# NO_1.net
KiCad netlist of a schematic drawn in Altium Designer
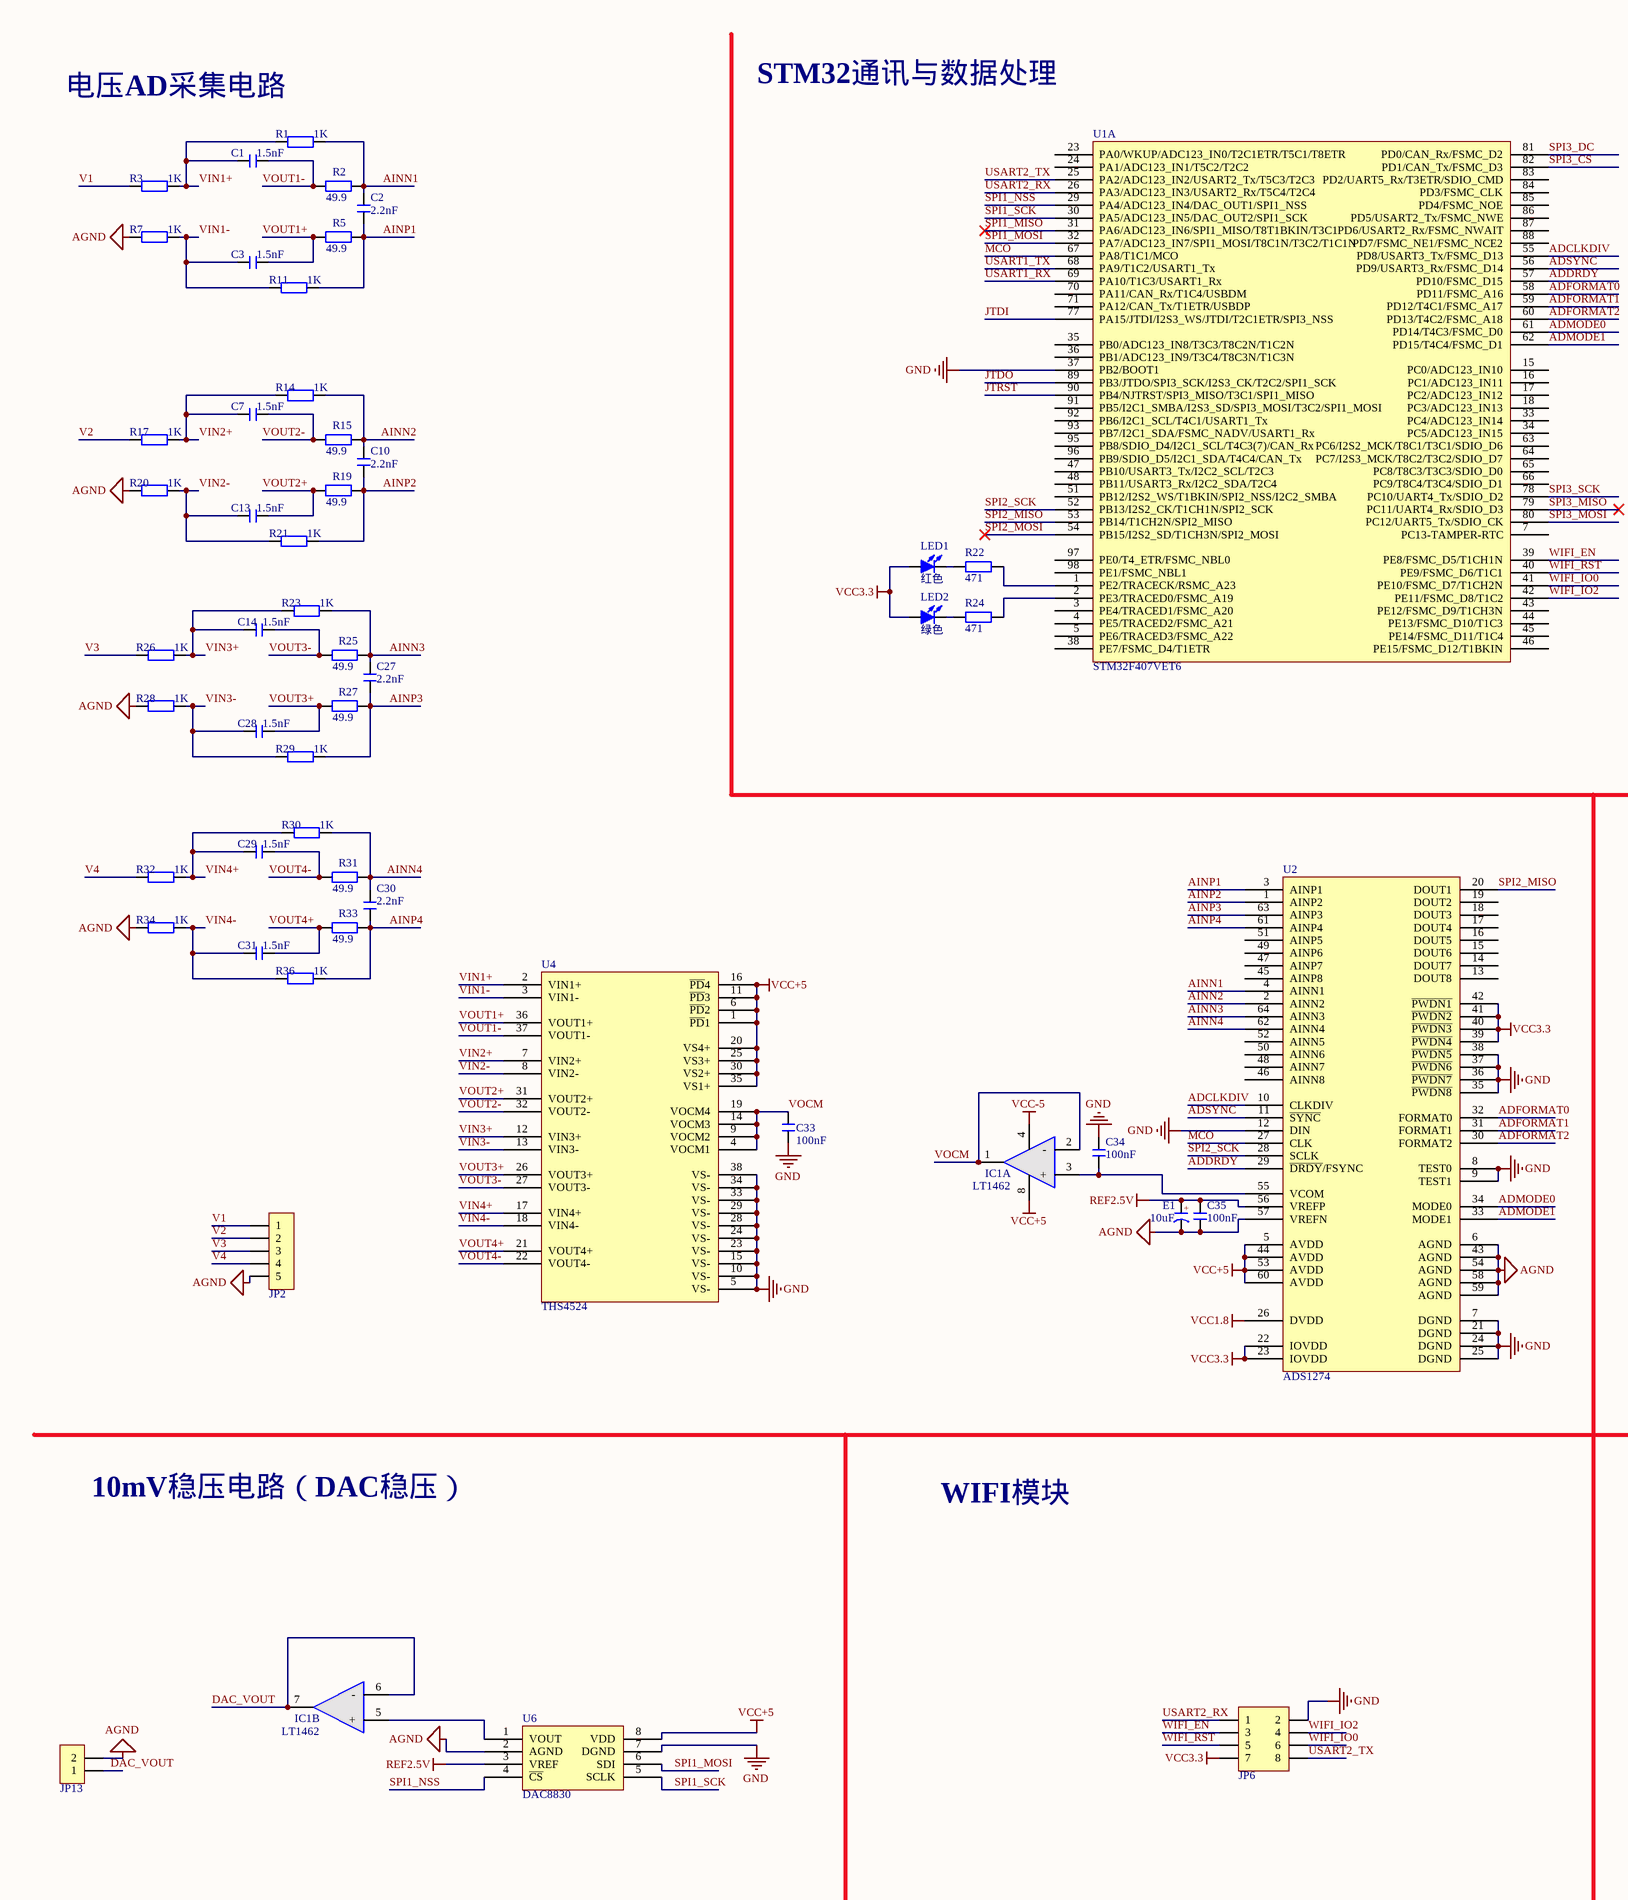
[diagram p0: NO.1 采集板.SchDoc, left]
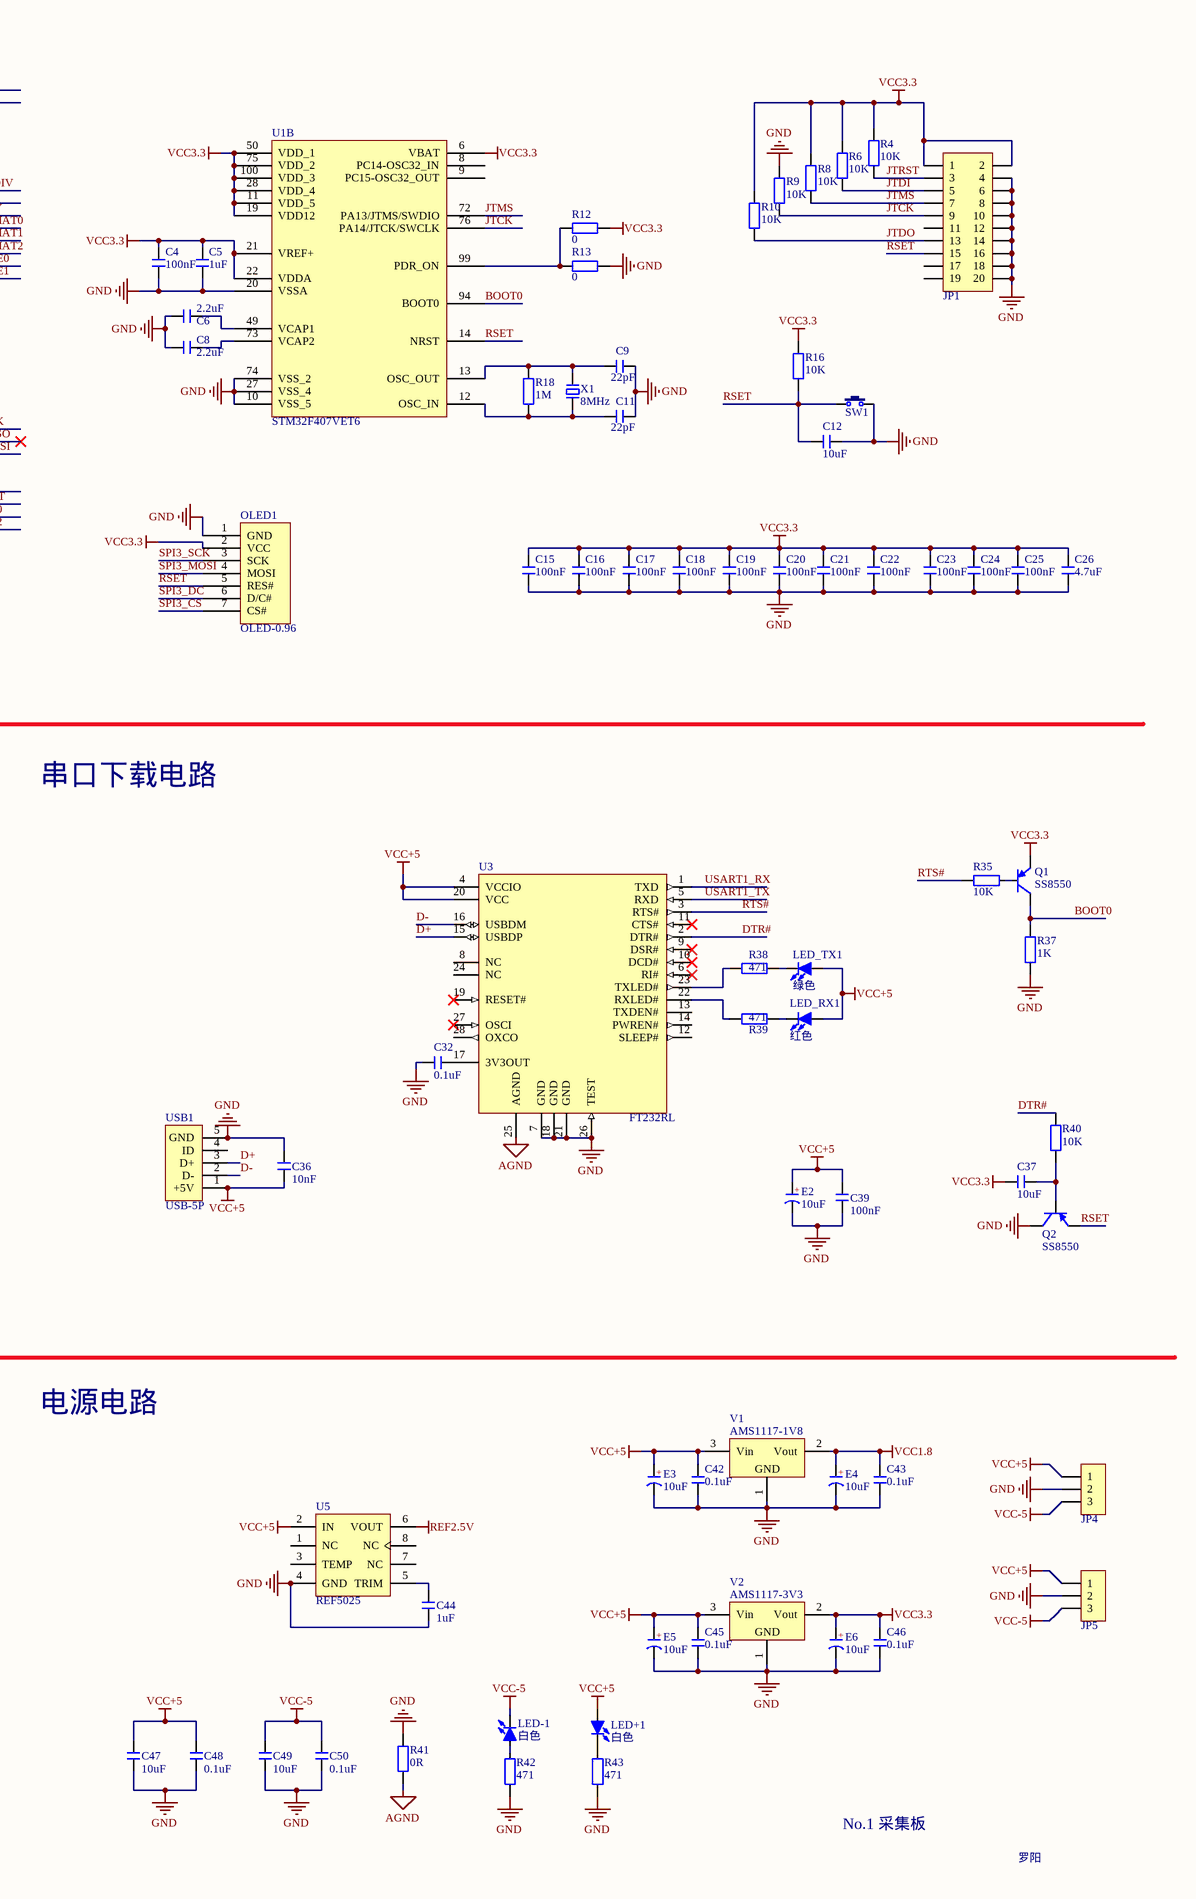
[diagram p1: NO.1 采集板.SchDoc, right]

(export (version "E")
  (design (tool "Eeschema 10.0.6"))
  (components
    (comp (ref "C1")
      (value "1.5nF")
      (footprint "C 0805_M")
      (description "无极性贴片电容")
      (fields (field (name "版权归属") "源创客"))
      (libsource (lib "3.1   - 电阻-电容-电感") (part "C"))
    )
    (comp (ref "C2")
      (value "2.2nF")
      (footprint "C 0805_M")
      (description "无极性贴片电容")
      (fields (field (name "版权归属") "源创客"))
      (libsource (lib "3.1   - 电阻-电容-电感") (part "C"))
    )
    (comp (ref "C3")
      (value "1.5nF")
      (footprint "C 0805_M")
      (description "无极性贴片电容")
      (fields (field (name "版权归属") "源创客"))
      (libsource (lib "3.1   - 电阻-电容-电感") (part "C"))
    )
    (comp (ref "C4")
      (value "100nF")
      (footprint "C 0805_M")
      (description "无极性贴片电容")
      (fields (field (name "版权归属") "源创客"))
      (libsource (lib "3.1   - 电阻-电容-电感") (part "C"))
    )
    (comp (ref "C5")
      (value "1uF")
      (footprint "C 0805_M")
      (description "无极性贴片电容")
      (fields (field (name "版权归属") "源创客"))
      (libsource (lib "3.1   - 电阻-电容-电感") (part "C"))
    )
    (comp (ref "C6")
      (value "2.2uF")
      (footprint "C 0805_M")
      (description "无极性贴片电容")
      (fields (field (name "版权归属") "源创客"))
      (libsource (lib "3.1   - 电阻-电容-电感") (part "C"))
    )
    (comp (ref "C7")
      (value "1.5nF")
      (footprint "C 0805_M")
      (description "无极性贴片电容")
      (fields (field (name "版权归属") "源创客"))
      (libsource (lib "3.1   - 电阻-电容-电感") (part "C"))
    )
    (comp (ref "C8")
      (value "2.2uF")
      (footprint "C 0805_M")
      (description "无极性贴片电容")
      (fields (field (name "版权归属") "源创客"))
      (libsource (lib "3.1   - 电阻-电容-电感") (part "C"))
    )
    (comp (ref "C9")
      (value "22pF")
      (footprint "C 0805_M")
      (description "无极性贴片电容")
      (fields (field (name "版权归属") "源创客"))
      (libsource (lib "3.1   - 电阻-电容-电感") (part "C"))
    )
    (comp (ref "C10")
      (value "2.2nF")
      (footprint "C 0805_M")
      (description "无极性贴片电容")
      (fields (field (name "版权归属") "源创客"))
      (libsource (lib "3.1   - 电阻-电容-电感") (part "C"))
    )
    (comp (ref "C11")
      (value "22pF")
      (footprint "C 0805_M")
      (description "无极性贴片电容")
      (fields (field (name "版权归属") "源创客"))
      (libsource (lib "3.1   - 电阻-电容-电感") (part "C"))
    )
    (comp (ref "C12")
      (value "10uF")
      (footprint "C 0805_M")
      (description "无极性贴片电容")
      (fields (field (name "版权归属") "源创客"))
      (libsource (lib "3.1   - 电阻-电容-电感") (part "C"))
    )
    (comp (ref "C13")
      (value "1.5nF")
      (footprint "C 0805_M")
      (description "无极性贴片电容")
      (fields (field (name "版权归属") "源创客"))
      (libsource (lib "3.1   - 电阻-电容-电感") (part "C"))
    )
    (comp (ref "C14")
      (value "1.5nF")
      (footprint "C 0805_M")
      (description "无极性贴片电容")
      (fields (field (name "版权归属") "源创客"))
      (libsource (lib "3.1   - 电阻-电容-电感") (part "C"))
    )
    (comp (ref "C15")
      (value "100nF")
      (footprint "C 0805_M")
      (description "无极性贴片电容")
      (fields (field (name "版权归属") "源创客"))
      (libsource (lib "3.1   - 电阻-电容-电感") (part "C"))
    )
    (comp (ref "C16")
      (value "100nF")
      (footprint "C 0805_M")
      (description "无极性贴片电容")
      (fields (field (name "版权归属") "源创客"))
      (libsource (lib "3.1   - 电阻-电容-电感") (part "C"))
    )
    (comp (ref "C17")
      (value "100nF")
      (footprint "C 0805_M")
      (description "无极性贴片电容")
      (fields (field (name "版权归属") "源创客"))
      (libsource (lib "3.1   - 电阻-电容-电感") (part "C"))
    )
    (comp (ref "C18")
      (value "100nF")
      (footprint "C 0805_M")
      (description "无极性贴片电容")
      (fields (field (name "版权归属") "源创客"))
      (libsource (lib "3.1   - 电阻-电容-电感") (part "C"))
    )
    (comp (ref "C19")
      (value "100nF")
      (footprint "C 0805_M")
      (description "无极性贴片电容")
      (fields (field (name "版权归属") "源创客"))
      (libsource (lib "3.1   - 电阻-电容-电感") (part "C"))
    )
    (comp (ref "C20")
      (value "100nF")
      (footprint "C 0805_M")
      (description "无极性贴片电容")
      (fields (field (name "版权归属") "源创客"))
      (libsource (lib "3.1   - 电阻-电容-电感") (part "C"))
    )
    (comp (ref "C21")
      (value "100nF")
      (footprint "C 0805_M")
      (description "无极性贴片电容")
      (fields (field (name "版权归属") "源创客"))
      (libsource (lib "3.1   - 电阻-电容-电感") (part "C"))
    )
    (comp (ref "C22")
      (value "100nF")
      (footprint "C 0805_M")
      (description "无极性贴片电容")
      (fields (field (name "版权归属") "源创客"))
      (libsource (lib "3.1   - 电阻-电容-电感") (part "C"))
    )
    (comp (ref "C23")
      (value "100nF")
      (footprint "C 0805_M")
      (description "无极性贴片电容")
      (fields (field (name "版权归属") "源创客"))
      (libsource (lib "3.1   - 电阻-电容-电感") (part "C"))
    )
    (comp (ref "C24")
      (value "100nF")
      (footprint "C 0805_M")
      (description "无极性贴片电容")
      (fields (field (name "版权归属") "源创客"))
      (libsource (lib "3.1   - 电阻-电容-电感") (part "C"))
    )
    (comp (ref "C25")
      (value "100nF")
      (footprint "C 0805_M")
      (description "无极性贴片电容")
      (fields (field (name "版权归属") "源创客"))
      (libsource (lib "3.1   - 电阻-电容-电感") (part "C"))
    )
    (comp (ref "C26")
      (value "4.7uF")
      (footprint "C 0805_M")
      (description "无极性贴片电容")
      (fields (field (name "版权归属") "源创客"))
      (libsource (lib "3.1   - 电阻-电容-电感") (part "C"))
    )
    (comp (ref "C27")
      (value "2.2nF")
      (footprint "C 0805_M")
      (description "无极性贴片电容")
      (fields (field (name "版权归属") "源创客"))
      (libsource (lib "3.1   - 电阻-电容-电感") (part "C"))
    )
    (comp (ref "C28")
      (value "1.5nF")
      (footprint "C 0805_M")
      (description "无极性贴片电容")
      (fields (field (name "版权归属") "源创客"))
      (libsource (lib "3.1   - 电阻-电容-电感") (part "C"))
    )
    (comp (ref "C29")
      (value "1.5nF")
      (footprint "C 0805_M")
      (description "无极性贴片电容")
      (fields (field (name "版权归属") "源创客"))
      (libsource (lib "3.1   - 电阻-电容-电感") (part "C"))
    )
    (comp (ref "C30")
      (value "2.2nF")
      (footprint "C 0805_M")
      (description "无极性贴片电容")
      (fields (field (name "版权归属") "源创客"))
      (libsource (lib "3.1   - 电阻-电容-电感") (part "C"))
    )
    (comp (ref "C31")
      (value "1.5nF")
      (footprint "C 0805_M")
      (description "无极性贴片电容")
      (fields (field (name "版权归属") "源创客"))
      (libsource (lib "3.1   - 电阻-电容-电感") (part "C"))
    )
    (comp (ref "C32")
      (value "0.1uF")
      (footprint "C 0805_M")
      (description "无极性贴片电容")
      (fields (field (name "版权归属") "源创客"))
      (libsource (lib "3.1   - 电阻-电容-电感") (part "C"))
    )
    (comp (ref "C33")
      (value "100nF")
      (footprint "C 0805_M")
      (description "无极性贴片电容")
      (fields (field (name "版权归属") "源创客"))
      (libsource (lib "3.1   - 电阻-电容-电感") (part "C"))
    )
    (comp (ref "C34")
      (value "100nF")
      (footprint "C 0805_M")
      (description "无极性贴片电容")
      (fields (field (name "版权归属") "源创客"))
      (libsource (lib "3.1   - 电阻-电容-电感") (part "C"))
    )
    (comp (ref "C35")
      (value "100nF")
      (footprint "C 0805_M")
      (description "无极性贴片电容")
      (fields (field (name "版权归属") "源创客"))
      (libsource (lib "3.1   - 电阻-电容-电感") (part "C"))
    )
    (comp (ref "C36")
      (value "10nF")
      (footprint "C 0805_M")
      (description "无极性贴片电容")
      (fields (field (name "版权归属") "源创客"))
      (libsource (lib "3.1   - 电阻-电容-电感") (part "C"))
    )
    (comp (ref "C37")
      (value "10uF")
      (footprint "C 0805_M")
      (description "无极性贴片电容")
      (fields (field (name "版权归属") "源创客"))
      (libsource (lib "3.1   - 电阻-电容-电感") (part "C"))
    )
    (comp (ref "C39")
      (value "100nF")
      (footprint "C 0805_M")
      (description "无极性贴片电容")
      (fields (field (name "版权归属") "源创客"))
      (libsource (lib "3.1   - 电阻-电容-电感") (part "C"))
    )
    (comp (ref "C42")
      (value "0.1uF")
      (footprint "C 0805_M")
      (description "无极性贴片电容")
      (fields (field (name "版权归属") "源创客"))
      (libsource (lib "3.1   - 电阻-电容-电感") (part "C"))
    )
    (comp (ref "C43")
      (value "0.1uF")
      (footprint "C 0805_M")
      (description "无极性贴片电容")
      (fields (field (name "版权归属") "源创客"))
      (libsource (lib "3.1   - 电阻-电容-电感") (part "C"))
    )
    (comp (ref "C44")
      (value "1uF")
      (footprint "C 0805_M")
      (description "无极性贴片电容")
      (fields (field (name "版权归属") "源创客"))
      (libsource (lib "3.1   - 电阻-电容-电感") (part "C"))
    )
    (comp (ref "C45")
      (value "0.1uF")
      (footprint "C 0805_M")
      (description "无极性贴片电容")
      (fields (field (name "版权归属") "源创客"))
      (libsource (lib "3.1   - 电阻-电容-电感") (part "C"))
    )
    (comp (ref "C46")
      (value "0.1uF")
      (footprint "C 0805_M")
      (description "无极性贴片电容")
      (fields (field (name "版权归属") "源创客"))
      (libsource (lib "3.1   - 电阻-电容-电感") (part "C"))
    )
    (comp (ref "C47")
      (value "10uF")
      (footprint "C 0805_M")
      (description "无极性贴片电容")
      (fields (field (name "版权归属") "源创客"))
      (libsource (lib "3.1   - 电阻-电容-电感") (part "C"))
    )
    (comp (ref "C48")
      (value "0.1uF")
      (footprint "C 0805_M")
      (description "无极性贴片电容")
      (fields (field (name "版权归属") "源创客"))
      (libsource (lib "3.1   - 电阻-电容-电感") (part "C"))
    )
    (comp (ref "C49")
      (value "10uF")
      (footprint "C 0805_M")
      (description "无极性贴片电容")
      (fields (field (name "版权归属") "源创客"))
      (libsource (lib "3.1   - 电阻-电容-电感") (part "C"))
    )
    (comp (ref "C50")
      (value "0.1uF")
      (footprint "C 0805_M")
      (description "无极性贴片电容")
      (fields (field (name "版权归属") "源创客"))
      (libsource (lib "3.1   - 电阻-电容-电感") (part "C"))
    )
    (comp (ref "E1")
      (value "10uF")
      (footprint "CD A(3216)")
      (description "贴片钽电容")
      (fields (field (name "版权归属") "源创客"))
      (libsource (lib "3.1   - 电阻-电容-电感") (part "C-CD"))
    )
    (comp (ref "E2")
      (value "10uF")
      (footprint "CD A(3216)")
      (description "贴片电解电容")
      (fields (field (name "版权归属") "源创客"))
      (libsource (lib "3.1   - 电阻-电容-电感") (part "C-CM"))
    )
    (comp (ref "E3")
      (value "10uF")
      (footprint "CD A(3216)")
      (description "贴片钽电容")
      (fields (field (name "版权归属") "源创客"))
      (libsource (lib "3.1   - 电阻-电容-电感") (part "C-CD"))
    )
    (comp (ref "E4")
      (value "10uF")
      (footprint "CD A(3216)")
      (description "贴片钽电容")
      (fields (field (name "版权归属") "源创客"))
      (libsource (lib "3.1   - 电阻-电容-电感") (part "C-CD"))
    )
    (comp (ref "E5")
      (value "10uF")
      (footprint "CD A(3216)")
      (description "贴片钽电容")
      (fields (field (name "版权归属") "源创客"))
      (libsource (lib "3.1   - 电阻-电容-电感") (part "C-CD"))
    )
    (comp (ref "E6")
      (value "10uF")
      (footprint "CD A(3216)")
      (description "贴片钽电容")
      (fields (field (name "版权归属") "源创客"))
      (libsource (lib "3.1   - 电阻-电容-电感") (part "C-CD"))
    )
    (comp (ref "IC1")
      (value "LT1462")
      (footprint "SOP8_N")
      (description "双运放")
      (fields (field (name "版权归属") "源创客"))
      (libsource (lib "1.1   - IC芯片") (part "LT1678"))
    )
    (comp (ref "JP1")
      (value "Header 2X10")
      (footprint "IDC2.54-LI-2x10P")
      (description "10*2P接插件")
      (fields (field (name "版权归属") "源创客"))
      (libsource (lib "4.5   - 接插件-脚距2.54") (part "Header 10X2"))
    )
    (comp (ref "JP2")
      (value "HDR-1X5")
      (footprint "XH2.54-WI-5P")
      (description "5P接插件")
      (fields (field (name "版权归属") "源创客"))
      (libsource (lib "4.5   - 接插件-脚距2.54") (part "Header 5"))
    )
    (comp (ref "JP4")
      (value "HDR-1X3")
      (footprint "XH2.54-WI-3P")
      (description "3P接插件")
      (fields (field (name "版权归属") "源创客"))
      (libsource (lib "4.2   - 接插件-脚距1.25") (part "Header 3"))
    )
    (comp (ref "JP5")
      (value "HDR-1X3")
      (footprint "XH2.54-WI-3P")
      (description "3P接插件")
      (fields (field (name "版权归属") "源创客"))
      (libsource (lib "4.2   - 接插件-脚距1.25") (part "Header 3"))
    )
    (comp (ref "JP6")
      (value "Header 4X2")
      (footprint "HDR2.54-LI-2x4P")
      (description "4*2P接插件")
      (fields (field (name "版权归属") "源创客"))
      (libsource (lib "4.5   - 接插件-脚距2.54") (part "Header 4X2"))
    )
    (comp (ref "JP13")
      (value "HDR-1X2")
      (footprint "XH2.54-WI-2P")
      (description "2P接插件")
      (fields (field (name "版权归属") "源创客"))
      (libsource (lib "4.5   - 接插件-脚距2.54") (part "Header 2"))
    )
    (comp (ref "LED+1")
      (value "白色")
      (footprint "LED 0805W")
      (description "贴片LED")
      (fields (field (name "版权归属") "源创客"))
      (libsource (lib "9.1   - LED") (part "LED-SMD"))
    )
    (comp (ref "LED-1")
      (value "白色")
      (footprint "LED 0805W")
      (description "贴片LED")
      (fields (field (name "版权归属") "源创客"))
      (libsource (lib "9.1   - LED") (part "LED-SMD"))
    )
    (comp (ref "LED1")
      (value "红色")
      (footprint "LED 0805R")
      (description "贴片LED")
      (fields (field (name "版权归属") "源创客"))
      (libsource (lib "9.1   - LED") (part "LED-SMD"))
    )
    (comp (ref "LED2")
      (value "绿色")
      (footprint "LED 0805G")
      (description "贴片LED")
      (fields (field (name "版权归属") "源创客"))
      (libsource (lib "9.1   - LED") (part "LED-SMD"))
    )
    (comp (ref "LED_RX1")
      (value "红色")
      (footprint "LED 0805R")
      (description "贴片LED")
      (fields (field (name "版权归属") "源创客"))
      (libsource (lib "9.1   - LED") (part "LED-SMD"))
    )
    (comp (ref "LED_TX1")
      (value "绿色")
      (footprint "LED 0805G")
      (description "贴片LED")
      (fields (field (name "版权归属") "源创客"))
      (libsource (lib "9.1   - LED") (part "LED-SMD"))
    )
    (comp (ref "OLED1") (value "OLED-0.96") (footprint "OLED") (libsource (lib "Schlib1") (part "OLED-0.96")))
    (comp (ref "Q1")
      (value "SS8550")
      (footprint "SOT23-3M")
      (description "高频放大-PNP型")
      (fields (field (name "版权归属") "源创客"))
      (libsource (lib "6.2   - 三极管") (part "8550-SMD"))
    )
    (comp (ref "Q2")
      (value "SS8550")
      (footprint "SOT23-3M")
      (description "高频放大-PNP型")
      (fields (field (name "版权归属") "源创客"))
      (libsource (lib "6.2   - 三极管") (part "8550-SMD"))
    )
    (comp (ref "R1")
      (value "1K")
      (footprint "R 0805_M")
      (description "贴片电阻")
      (fields (field (name "版权归属") "源创客"))
      (libsource (lib "3.1   - 电阻-电容-电感") (part "R"))
    )
    (comp (ref "R2")
      (value "49.9")
      (footprint "R 0805_M")
      (description "贴片电阻")
      (fields (field (name "版权归属") "源创客"))
      (libsource (lib "3.1   - 电阻-电容-电感") (part "R"))
    )
    (comp (ref "R3")
      (value "1K")
      (footprint "R 0805_M")
      (description "贴片电阻")
      (fields (field (name "版权归属") "源创客"))
      (libsource (lib "3.1   - 电阻-电容-电感") (part "R"))
    )
    (comp (ref "R4")
      (value "10K")
      (footprint "R 0805_M")
      (description "贴片电阻")
      (fields (field (name "版权归属") "源创客"))
      (libsource (lib "3.1   - 电阻-电容-电感") (part "R"))
    )
    (comp (ref "R5")
      (value "49.9")
      (footprint "R 0805_M")
      (description "贴片电阻")
      (fields (field (name "版权归属") "源创客"))
      (libsource (lib "3.1   - 电阻-电容-电感") (part "R"))
    )
    (comp (ref "R6")
      (value "10K")
      (footprint "R 0805_M")
      (description "贴片电阻")
      (fields (field (name "版权归属") "源创客"))
      (libsource (lib "3.1   - 电阻-电容-电感") (part "R"))
    )
    (comp (ref "R7")
      (value "1K")
      (footprint "R 0805_M")
      (description "贴片电阻")
      (fields (field (name "版权归属") "源创客"))
      (libsource (lib "3.1   - 电阻-电容-电感") (part "R"))
    )
    (comp (ref "R8")
      (value "10K")
      (footprint "R 0805_M")
      (description "贴片电阻")
      (fields (field (name "版权归属") "源创客"))
      (libsource (lib "3.1   - 电阻-电容-电感") (part "R"))
    )
    (comp (ref "R9")
      (value "10K")
      (footprint "R 0805_M")
      (description "贴片电阻")
      (fields (field (name "版权归属") "源创客"))
      (libsource (lib "3.1   - 电阻-电容-电感") (part "R"))
    )
    (comp (ref "R10")
      (value "10K")
      (footprint "R 0805_M")
      (description "贴片电阻")
      (fields (field (name "版权归属") "源创客"))
      (libsource (lib "3.1   - 电阻-电容-电感") (part "R"))
    )
    (comp (ref "R11")
      (value "1K")
      (footprint "R 0805_M")
      (description "贴片电阻")
      (fields (field (name "版权归属") "源创客"))
      (libsource (lib "3.1   - 电阻-电容-电感") (part "R"))
    )
    (comp (ref "R12")
      (value "0")
      (footprint "R 0805_M")
      (description "贴片电阻")
      (fields (field (name "版权归属") "源创客"))
      (libsource (lib "3.1   - 电阻-电容-电感") (part "R"))
    )
    (comp (ref "R13")
      (value "0")
      (footprint "R 0805_M")
      (description "贴片电阻")
      (fields (field (name "版权归属") "源创客"))
      (libsource (lib "3.1   - 电阻-电容-电感") (part "R"))
    )
    (comp (ref "R14")
      (value "1K")
      (footprint "R 0805_M")
      (description "贴片电阻")
      (fields (field (name "版权归属") "源创客"))
      (libsource (lib "3.1   - 电阻-电容-电感") (part "R"))
    )
    (comp (ref "R15")
      (value "49.9")
      (footprint "R 0805_M")
      (description "贴片电阻")
      (fields (field (name "版权归属") "源创客"))
      (libsource (lib "3.1   - 电阻-电容-电感") (part "R"))
    )
    (comp (ref "R16")
      (value "10K")
      (footprint "R 0805_M")
      (description "贴片电阻")
      (fields (field (name "版权归属") "源创客"))
      (libsource (lib "3.1   - 电阻-电容-电感") (part "R"))
    )
    (comp (ref "R17")
      (value "1K")
      (footprint "R 0805_M")
      (description "贴片电阻")
      (fields (field (name "版权归属") "源创客"))
      (libsource (lib "3.1   - 电阻-电容-电感") (part "R"))
    )
    (comp (ref "R18")
      (value "1M")
      (footprint "R 0805_M")
      (description "贴片电阻")
      (fields (field (name "版权归属") "源创客"))
      (libsource (lib "3.1   - 电阻-电容-电感") (part "R"))
    )
    (comp (ref "R19")
      (value "49.9")
      (footprint "R 0805_M")
      (description "贴片电阻")
      (fields (field (name "版权归属") "源创客"))
      (libsource (lib "3.1   - 电阻-电容-电感") (part "R"))
    )
    (comp (ref "R20")
      (value "1K")
      (footprint "R 0805_M")
      (description "贴片电阻")
      (fields (field (name "版权归属") "源创客"))
      (libsource (lib "3.1   - 电阻-电容-电感") (part "R"))
    )
    (comp (ref "R21")
      (value "1K")
      (footprint "R 0805_M")
      (description "贴片电阻")
      (fields (field (name "版权归属") "源创客"))
      (libsource (lib "3.1   - 电阻-电容-电感") (part "R"))
    )
    (comp (ref "R22")
      (value "471")
      (footprint "R 0805_M")
      (description "贴片电阻")
      (fields (field (name "版权归属") "源创客"))
      (libsource (lib "3.1   - 电阻-电容-电感") (part "R"))
    )
    (comp (ref "R23")
      (value "1K")
      (footprint "R 0805_M")
      (description "贴片电阻")
      (fields (field (name "版权归属") "源创客"))
      (libsource (lib "3.1   - 电阻-电容-电感") (part "R"))
    )
    (comp (ref "R24")
      (value "471")
      (footprint "R 0805_M")
      (description "贴片电阻")
      (fields (field (name "版权归属") "源创客"))
      (libsource (lib "3.1   - 电阻-电容-电感") (part "R"))
    )
    (comp (ref "R25")
      (value "49.9")
      (footprint "R 0805_M")
      (description "贴片电阻")
      (fields (field (name "版权归属") "源创客"))
      (libsource (lib "3.1   - 电阻-电容-电感") (part "R"))
    )
    (comp (ref "R26")
      (value "1K")
      (footprint "R 0805_M")
      (description "贴片电阻")
      (fields (field (name "版权归属") "源创客"))
      (libsource (lib "3.1   - 电阻-电容-电感") (part "R"))
    )
    (comp (ref "R27")
      (value "49.9")
      (footprint "R 0805_M")
      (description "贴片电阻")
      (fields (field (name "版权归属") "源创客"))
      (libsource (lib "3.1   - 电阻-电容-电感") (part "R"))
    )
    (comp (ref "R28")
      (value "1K")
      (footprint "R 0805_M")
      (description "贴片电阻")
      (fields (field (name "版权归属") "源创客"))
      (libsource (lib "3.1   - 电阻-电容-电感") (part "R"))
    )
    (comp (ref "R29")
      (value "1K")
      (footprint "R 0805_M")
      (description "贴片电阻")
      (fields (field (name "版权归属") "源创客"))
      (libsource (lib "3.1   - 电阻-电容-电感") (part "R"))
    )
    (comp (ref "R30")
      (value "1K")
      (footprint "R 0805_M")
      (description "贴片电阻")
      (fields (field (name "版权归属") "源创客"))
      (libsource (lib "3.1   - 电阻-电容-电感") (part "R"))
    )
    (comp (ref "R31")
      (value "49.9")
      (footprint "R 0805_M")
      (description "贴片电阻")
      (fields (field (name "版权归属") "源创客"))
      (libsource (lib "3.1   - 电阻-电容-电感") (part "R"))
    )
    (comp (ref "R32")
      (value "1K")
      (footprint "R 0805_M")
      (description "贴片电阻")
      (fields (field (name "版权归属") "源创客"))
      (libsource (lib "3.1   - 电阻-电容-电感") (part "R"))
    )
    (comp (ref "R33")
      (value "49.9")
      (footprint "R 0805_M")
      (description "贴片电阻")
      (fields (field (name "版权归属") "源创客"))
      (libsource (lib "3.1   - 电阻-电容-电感") (part "R"))
    )
    (comp (ref "R34")
      (value "1K")
      (footprint "R 0805_M")
      (description "贴片电阻")
      (fields (field (name "版权归属") "源创客"))
      (libsource (lib "3.1   - 电阻-电容-电感") (part "R"))
    )
    (comp (ref "R35")
      (value "10K")
      (footprint "R 0805_M")
      (description "贴片电阻")
      (fields (field (name "版权归属") "源创客"))
      (libsource (lib "3.1   - 电阻-电容-电感") (part "R"))
    )
    (comp (ref "R36")
      (value "1K")
      (footprint "R 0805_M")
      (description "贴片电阻")
      (fields (field (name "版权归属") "源创客"))
      (libsource (lib "3.1   - 电阻-电容-电感") (part "R"))
    )
    (comp (ref "R37")
      (value "1K")
      (footprint "R 0805_M")
      (description "贴片电阻")
      (fields (field (name "版权归属") "源创客"))
      (libsource (lib "3.1   - 电阻-电容-电感") (part "R"))
    )
    (comp (ref "R38")
      (value "471")
      (footprint "R 0805_M")
      (description "贴片电阻")
      (fields (field (name "版权归属") "源创客"))
      (libsource (lib "3.1   - 电阻-电容-电感") (part "R"))
    )
    (comp (ref "R39")
      (value "471")
      (footprint "R 0805_M")
      (description "贴片电阻")
      (fields (field (name "版权归属") "源创客"))
      (libsource (lib "3.1   - 电阻-电容-电感") (part "R"))
    )
    (comp (ref "R40")
      (value "10K")
      (footprint "R 0805_M")
      (description "贴片电阻")
      (fields (field (name "版权归属") "源创客"))
      (libsource (lib "3.1   - 电阻-电容-电感") (part "R"))
    )
    (comp (ref "R41")
      (value "0R")
      (footprint "R 0805_M")
      (description "贴片电阻")
      (fields (field (name "版权归属") "源创客"))
      (libsource (lib "3.1   - 电阻-电容-电感") (part "R"))
    )
    (comp (ref "R42")
      (value "471")
      (footprint "R 0805_M")
      (description "贴片电阻")
      (fields (field (name "版权归属") "源创客"))
      (libsource (lib "3.1   - 电阻-电容-电感") (part "R"))
    )
    (comp (ref "R43")
      (value "471")
      (footprint "R 0805_M")
      (description "贴片电阻")
      (fields (field (name "版权归属") "源创客"))
      (libsource (lib "3.1   - 电阻-电容-电感") (part "R"))
    )
    (comp (ref "SW1")
      (value "3x6x5")
      (footprint "TSW SMD-3*6*2.5")
      (description "3x6轻触开关")
      (fields (field (name "版权归属") "源创客"))
      (libsource (lib "5.1   - 按键-开关") (part "TSW 3x6"))
    )
    (comp (ref "U1")
      (value "STM32F407VET6")
      (footprint "LQFP-100_M")
      (description "STM32单片机100引脚")
      (libsource (lib "STM32芯片") (part "STM32F407V"))
    )
    (comp (ref "U2")
      (value "ADS1274")
      (footprint "TQFP64-10*10")
      (libsource (lib "Schlib1") (part "ADS1274/ADS1278"))
    )
    (comp (ref "U3")
      (value "FT232RL")
      (footprint "SSOP28_N")
      (description "USB转串口")
      (fields (field (name "版权归属") "源创客"))
      (libsource (lib "1.1   - IC芯片") (part "FT232RL"))
    )
    (comp (ref "U4")
      (value "THS4524")
      (footprint "TSSOP-38 - duplicate")
      (libsource (lib "Schlib1") (part "THS4524"))
    )
    (comp (ref "U5")
      (value "REF5025")
      (footprint "SOP8_M")
      (description "高精度电压基准")
      (fields (field (name "版权归属") "源创客"))
      (libsource (lib "1.3   - 电源类芯片") (part "REF5040"))
    )
    (comp (ref "U6") (value "DAC8830") (footprint "SOP8") (libsource (lib "Schlib1") (part "DAC8830")))
    (comp (ref "USB1")
      (value "USB-5P")
      (footprint "USB-MICRO_D")
      (description "微型USB母座")
      (fields (field (name "版权归属") "源创客"))
      (libsource (lib "4.1   - 接口类") (part "USB-5P"))
    )
    (comp (ref "V1")
      (value "AMS1117-1V8")
      (footprint "SOT223_M")
      (description "三端稳压芯片")
      (fields (field (name "版权归属") "源创客"))
      (libsource (lib "1.3   - 电源类芯片") (part "AMS1117"))
    )
    (comp (ref "V2")
      (value "AMS1117-3V3")
      (footprint "SOT223_M")
      (description "三端稳压芯片")
      (fields (field (name "版权归属") "源创客"))
      (libsource (lib "1.3   - 电源类芯片") (part "AMS1117"))
    )
    (comp (ref "X1")
      (value "8MHz")
      (footprint "OSC HC-49S")
      (description "2脚无源脚晶振")
      (fields (field (name "版权归属") "源创客"))
      (libsource (lib "10.1 - 保险丝-晶振") (part "XTAL-2P"))
    )
  )
  (nets
    (net (code "1") (name "/ADCLKDIV") (class "Default")
      (node (ref "U1") (pin "55") (pinfunction "PD8/USART3_Tx/FSMC_D13_55") (pintype "passive"))
      (node (ref "U2") (pin "10") (pinfunction "CLKDIV_10") (pintype "passive"))
    )
    (net (code "2") (name "/ADDRDY") (class "Default")
      (node (ref "U1") (pin "57") (pinfunction "PD10/FSMC_D15_57") (pintype "passive"))
      (node (ref "U2") (pin "29") (pinfunction "~{DRDY}/FSYNC_29") (pintype "passive"))
    )
    (net (code "3") (name "/ADFORMAT0") (class "Default")
      (node (ref "U1") (pin "58") (pinfunction "PD11/FSMC_A16_58") (pintype "passive"))
      (node (ref "U2") (pin "32") (pinfunction "FORMAT0_32") (pintype "passive"))
    )
    (net (code "4") (name "/ADFORMAT1") (class "Default")
      (node (ref "U1") (pin "59") (pinfunction "PD12/T4C1/FSMC_A17_59") (pintype "passive"))
      (node (ref "U2") (pin "31") (pinfunction "FORMAT1_31") (pintype "passive"))
    )
    (net (code "5") (name "/ADFORMAT2") (class "Default")
      (node (ref "U1") (pin "60") (pinfunction "PD13/T4C2/FSMC_A18_60") (pintype "passive"))
      (node (ref "U2") (pin "30") (pinfunction "FORMAT2_30") (pintype "passive"))
    )
    (net (code "6") (name "/ADMODE0") (class "Default")
      (node (ref "U1") (pin "61") (pinfunction "PD14/T4C3/FSMC_D0_61") (pintype "passive"))
      (node (ref "U2") (pin "34") (pinfunction "MODE0_34") (pintype "passive"))
    )
    (net (code "7") (name "/ADMODE1") (class "Default")
      (node (ref "U1") (pin "62") (pinfunction "PD15/T4C4/FSMC_D1_62") (pintype "passive"))
      (node (ref "U2") (pin "33") (pinfunction "MODE1_33") (pintype "passive"))
    )
    (net (code "8") (name "/ADSYNC") (class "Default")
      (node (ref "U1") (pin "56") (pinfunction "PD9/USART3_Rx/FSMC_D14_56") (pintype "passive"))
      (node (ref "U2") (pin "11") (pinfunction "~{SYNC}_11") (pintype "passive"))
    )
    (net (code "9") (name "/AINN1") (class "Default")
      (node (ref "C2") (pin "1") (pinfunction "1_1") (pintype "passive"))
      (node (ref "R1") (pin "2") (pinfunction "2_2") (pintype "passive"))
      (node (ref "R2") (pin "2") (pinfunction "2_2") (pintype "passive"))
      (node (ref "U2") (pin "4") (pinfunction "AINN1_4") (pintype "passive"))
    )
    (net (code "10") (name "/AINN2") (class "Default")
      (node (ref "C10") (pin "1") (pinfunction "1_1") (pintype "passive"))
      (node (ref "R14") (pin "2") (pinfunction "2_2") (pintype "passive"))
      (node (ref "R15") (pin "2") (pinfunction "2_2") (pintype "passive"))
      (node (ref "U2") (pin "2") (pinfunction "AINN2_2") (pintype "passive"))
    )
    (net (code "11") (name "/AINN3") (class "Default")
      (node (ref "C27") (pin "1") (pinfunction "1_1") (pintype "passive"))
      (node (ref "R23") (pin "2") (pinfunction "2_2") (pintype "passive"))
      (node (ref "R25") (pin "2") (pinfunction "2_2") (pintype "passive"))
      (node (ref "U2") (pin "64") (pinfunction "AINN3_64") (pintype "passive"))
    )
    (net (code "12") (name "/AINN4") (class "Default")
      (node (ref "C30") (pin "1") (pinfunction "1_1") (pintype "passive"))
      (node (ref "R30") (pin "2") (pinfunction "2_2") (pintype "passive"))
      (node (ref "R31") (pin "2") (pinfunction "2_2") (pintype "passive"))
      (node (ref "U2") (pin "62") (pinfunction "AINN4_62") (pintype "passive"))
    )
    (net (code "13") (name "/AINP1") (class "Default")
      (node (ref "C2") (pin "2") (pinfunction "2_2") (pintype "passive"))
      (node (ref "R11") (pin "2") (pinfunction "2_2") (pintype "passive"))
      (node (ref "R5") (pin "2") (pinfunction "2_2") (pintype "passive"))
      (node (ref "U2") (pin "3") (pinfunction "AINP1_3") (pintype "passive"))
    )
    (net (code "14") (name "/AINP2") (class "Default")
      (node (ref "C10") (pin "2") (pinfunction "2_2") (pintype "passive"))
      (node (ref "R19") (pin "2") (pinfunction "2_2") (pintype "passive"))
      (node (ref "R21") (pin "2") (pinfunction "2_2") (pintype "passive"))
      (node (ref "U2") (pin "1") (pinfunction "AINP2_1") (pintype "passive"))
    )
    (net (code "15") (name "/AINP3") (class "Default")
      (node (ref "C27") (pin "2") (pinfunction "2_2") (pintype "passive"))
      (node (ref "R27") (pin "2") (pinfunction "2_2") (pintype "passive"))
      (node (ref "R29") (pin "2") (pinfunction "2_2") (pintype "passive"))
      (node (ref "U2") (pin "63") (pinfunction "AINP3_63") (pintype "passive"))
    )
    (net (code "16") (name "/AINP4") (class "Default")
      (node (ref "C30") (pin "2") (pinfunction "2_2") (pintype "passive"))
      (node (ref "R33") (pin "2") (pinfunction "2_2") (pintype "passive"))
      (node (ref "R36") (pin "2") (pinfunction "2_2") (pintype "passive"))
      (node (ref "U2") (pin "61") (pinfunction "AINP4_61") (pintype "passive"))
    )
    (net (code "17") (name "/BOOT0") (class "Default")
      (node (ref "Q1") (pin "3") (pinfunction "C_3") (pintype "passive"))
      (node (ref "R37") (pin "2") (pinfunction "2_2") (pintype "passive"))
      (node (ref "U1") (pin "94") (pinfunction "BOOT0_94") (pintype "passive"))
    )
    (net (code "18") (name "/D+") (class "Default")
      (node (ref "U3") (pin "15") (pinfunction "USBDP_15") (pintype "bidirectional"))
      (node (ref "USB1") (pin "3") (pinfunction "D+_3") (pintype "passive"))
    )
    (net (code "19") (name "/D-") (class "Default")
      (node (ref "U3") (pin "16") (pinfunction "USBDM_16") (pintype "bidirectional"))
      (node (ref "USB1") (pin "2") (pinfunction "D-_2") (pintype "passive"))
    )
    (net (code "20") (name "/DAC_VOUT") (class "Default")
      (node (ref "IC1") (pin "6") (pinfunction "-_6") (pintype "passive"))
      (node (ref "IC1") (pin "7") (pinfunction "OUT2_7") (pintype "passive"))
      (node (ref "JP13") (pin "1") (pinfunction "1_1") (pintype "passive"))
    )
    (net (code "21") (name "/DTR#") (class "Default")
      (node (ref "R40") (pin "2") (pinfunction "2_2") (pintype "passive"))
      (node (ref "U3") (pin "2") (pinfunction "DTR#_2") (pintype "output"))
    )
    (net (code "22") (name "/JTCK") (class "Default")
      (node (ref "JP1") (pin "9") (pinfunction "9_9") (pintype "passive"))
      (node (ref "R9") (pin "2") (pinfunction "2_2") (pintype "passive"))
      (node (ref "U1") (pin "76") (pinfunction "PA14/JTCK/SWCLK_76") (pintype "passive"))
    )
    (net (code "23") (name "/JTDI") (class "Default")
      (node (ref "JP1") (pin "5") (pinfunction "5_5") (pintype "passive"))
      (node (ref "R6") (pin "2") (pinfunction "2_2") (pintype "passive"))
      (node (ref "U1") (pin "77") (pinfunction "PA15/JTDI/I2S3_WS/JTDI/T2C1ETR/SPI3_NSS_77") (pintype "passive"))
    )
    (net (code "24") (name "/JTDO") (class "Default")
      (node (ref "JP1") (pin "13") (pinfunction "13_13") (pintype "passive"))
      (node (ref "R10") (pin "2") (pinfunction "2_2") (pintype "passive"))
      (node (ref "U1") (pin "89") (pinfunction "PB3/JTDO/SPI3_SCK/I2S3_CK/T2C2/SPI1_SCK_89") (pintype "passive"))
    )
    (net (code "25") (name "/JTMS") (class "Default")
      (node (ref "JP1") (pin "7") (pinfunction "7_7") (pintype "passive"))
      (node (ref "R8") (pin "2") (pinfunction "2_2") (pintype "passive"))
      (node (ref "U1") (pin "72") (pinfunction "PA13/JTMS/SWDIO_72") (pintype "passive"))
    )
    (net (code "26") (name "/JTRST") (class "Default")
      (node (ref "JP1") (pin "3") (pinfunction "3_3") (pintype "passive"))
      (node (ref "R4") (pin "2") (pinfunction "2_2") (pintype "passive"))
      (node (ref "U1") (pin "90") (pinfunction "PB4/NJTRST/SPI3_MISO/T3C1/SPI1_MISO_90") (pintype "passive"))
    )
    (net (code "27") (name "/MCO") (class "Default")
      (node (ref "U1") (pin "67") (pinfunction "PA8/T1C1/MCO_67") (pintype "passive"))
      (node (ref "U2") (pin "27") (pinfunction "CLK_27") (pintype "passive"))
    )
    (net (code "28") (name "/RSET") (class "Default")
      (node (ref "C12") (pin "1") (pinfunction "1_1") (pintype "passive"))
      (node (ref "JP1") (pin "15") (pinfunction "15_15") (pintype "passive"))
      (node (ref "OLED1") (pin "5") (pinfunction "RES#_5") (pintype "passive"))
      (node (ref "Q2") (pin "2") (pinfunction "E_2") (pintype "passive"))
      (node (ref "R16") (pin "1") (pinfunction "1_1") (pintype "passive"))
      (node (ref "SW1") (pin "1") (pinfunction "1_1") (pintype "passive"))
      (node (ref "U1") (pin "14") (pinfunction "NRST_14") (pintype "passive"))
    )
    (net (code "29") (name "/RTS#") (class "Default")
      (node (ref "R35") (pin "1") (pinfunction "1_1") (pintype "passive"))
      (node (ref "U3") (pin "3") (pinfunction "RTS#_3") (pintype "output"))
    )
    (net (code "30") (name "/SPI1_MISO") (class "Default")
      (node (ref "U1") (pin "31") (pinfunction "PA6/ADC123_IN6/SPI1_MISO/T8T1BKIN/T3C1_31") (pintype "passive+no_connect"))
    )
    (net (code "31") (name "/SPI1_MOSI") (class "Default")
      (node (ref "U1") (pin "32") (pinfunction "PA7/ADC123_IN7/SPI1_MOSI/T8C1N/T3C2/T1C1N_32") (pintype "passive"))
      (node (ref "U6") (pin "6") (pinfunction "SDI_6") (pintype "passive"))
    )
    (net (code "32") (name "/SPI1_NSS") (class "Default")
      (node (ref "U1") (pin "29") (pinfunction "PA4/ADC123_IN4/DAC_OUT1/SPI1_NSS_29") (pintype "passive"))
      (node (ref "U6") (pin "4") (pinfunction "~{CS}_4") (pintype "passive"))
    )
    (net (code "33") (name "/SPI1_SCK") (class "Default")
      (node (ref "U1") (pin "30") (pinfunction "PA5/ADC123_IN5/DAC_OUT2/SPI1_SCK_30") (pintype "passive"))
      (node (ref "U6") (pin "5") (pinfunction "SCLK_5") (pintype "passive"))
    )
    (net (code "34") (name "/SPI2_MISO") (class "Default")
      (node (ref "U1") (pin "53") (pinfunction "PB14/T1CH2N/SPI2_MISO_53") (pintype "passive"))
      (node (ref "U2") (pin "20") (pinfunction "DOUT1_20") (pintype "passive"))
    )
    (net (code "35") (name "/SPI2_MOSI") (class "Default")
      (node (ref "U1") (pin "54") (pinfunction "PB15/I2S2_SD/T1CH3N/SPI2_MOSI_54") (pintype "passive+no_connect"))
    )
    (net (code "36") (name "/SPI2_SCK") (class "Default")
      (node (ref "U1") (pin "52") (pinfunction "PB13/I2S2_CK/T1CH1N/SPI2_SCK_52") (pintype "passive"))
      (node (ref "U2") (pin "28") (pinfunction "SCLK_28") (pintype "passive"))
    )
    (net (code "37") (name "/SPI3_CS") (class "Default")
      (node (ref "OLED1") (pin "7") (pinfunction "CS#_7") (pintype "passive"))
      (node (ref "U1") (pin "82") (pinfunction "PD1/CAN_Tx/FSMC_D3_82") (pintype "passive"))
    )
    (net (code "38") (name "/SPI3_DC") (class "Default")
      (node (ref "OLED1") (pin "6") (pinfunction "D/C#_6") (pintype "passive"))
      (node (ref "U1") (pin "81") (pinfunction "PD0/CAN_Rx/FSMC_D2_81") (pintype "passive"))
    )
    (net (code "39") (name "/SPI3_MISO") (class "Default")
      (node (ref "U1") (pin "79") (pinfunction "PC11/UART4_Rx/SDIO_D3_79") (pintype "passive+no_connect"))
    )
    (net (code "40") (name "/SPI3_MOSI") (class "Default")
      (node (ref "OLED1") (pin "4") (pinfunction "MOSI_4") (pintype "passive"))
      (node (ref "U1") (pin "80") (pinfunction "PC12/UART5_Tx/SDIO_CK_80") (pintype "passive"))
    )
    (net (code "41") (name "/SPI3_SCK") (class "Default")
      (node (ref "OLED1") (pin "3") (pinfunction "SCK_3") (pintype "passive"))
      (node (ref "U1") (pin "78") (pinfunction "PC10/UART4_Tx/SDIO_D2_78") (pintype "passive"))
    )
    (net (code "42") (name "/USART1_RX") (class "Default")
      (node (ref "U1") (pin "69") (pinfunction "PA10/T1C3/USART1_Rx_69") (pintype "passive"))
      (node (ref "U3") (pin "1") (pinfunction "TXD_1") (pintype "output"))
    )
    (net (code "43") (name "/USART1_TX") (class "Default")
      (node (ref "U1") (pin "68") (pinfunction "PA9/T1C2/USART1_Tx_68") (pintype "passive"))
      (node (ref "U3") (pin "5") (pinfunction "RXD_5") (pintype "input"))
    )
    (net (code "44") (name "/USART2_RX") (class "Default")
      (node (ref "JP6") (pin "1") (pinfunction "1_1") (pintype "passive"))
      (node (ref "U1") (pin "26") (pinfunction "PA3/ADC123_IN3/USART2_Rx/T5C4/T2C4_26") (pintype "passive"))
    )
    (net (code "45") (name "/USART2_TX") (class "Default")
      (node (ref "JP6") (pin "8") (pinfunction "8_8") (pintype "passive"))
      (node (ref "U1") (pin "25") (pinfunction "PA2/ADC123_IN2/USART2_Tx/T5C3/T2C3_25") (pintype "passive"))
    )
    (net (code "46") (name "/V1") (class "Default")
      (node (ref "JP2") (pin "1") (pinfunction "1_1") (pintype "passive"))
      (node (ref "R3") (pin "1") (pinfunction "1_1") (pintype "passive"))
    )
    (net (code "47") (name "/V2") (class "Default")
      (node (ref "JP2") (pin "2") (pinfunction "2_2") (pintype "passive"))
      (node (ref "R17") (pin "1") (pinfunction "1_1") (pintype "passive"))
    )
    (net (code "48") (name "/V3") (class "Default")
      (node (ref "JP2") (pin "3") (pinfunction "3_3") (pintype "passive"))
      (node (ref "R26") (pin "1") (pinfunction "1_1") (pintype "passive"))
    )
    (net (code "49") (name "/V4") (class "Default")
      (node (ref "JP2") (pin "4") (pinfunction "4_4") (pintype "passive"))
      (node (ref "R32") (pin "1") (pinfunction "1_1") (pintype "passive"))
    )
    (net (code "50") (name "/VIN1+") (class "Default")
      (node (ref "C1") (pin "2") (pinfunction "2_2") (pintype "passive"))
      (node (ref "R1") (pin "1") (pinfunction "1_1") (pintype "passive"))
      (node (ref "R3") (pin "2") (pinfunction "2_2") (pintype "passive"))
      (node (ref "U4") (pin "2") (pinfunction "VIN1+_2") (pintype "passive"))
    )
    (net (code "51") (name "/VIN1-") (class "Default")
      (node (ref "C3") (pin "2") (pinfunction "2_2") (pintype "passive"))
      (node (ref "R11") (pin "1") (pinfunction "1_1") (pintype "passive"))
      (node (ref "R7") (pin "2") (pinfunction "2_2") (pintype "passive"))
      (node (ref "U4") (pin "3") (pinfunction "VIN1-_3") (pintype "passive"))
    )
    (net (code "52") (name "/VIN2+") (class "Default")
      (node (ref "C7") (pin "2") (pinfunction "2_2") (pintype "passive"))
      (node (ref "R14") (pin "1") (pinfunction "1_1") (pintype "passive"))
      (node (ref "R17") (pin "2") (pinfunction "2_2") (pintype "passive"))
      (node (ref "U4") (pin "7") (pinfunction "VIN2+_7") (pintype "passive"))
    )
    (net (code "53") (name "/VIN2-") (class "Default")
      (node (ref "C13") (pin "2") (pinfunction "2_2") (pintype "passive"))
      (node (ref "R20") (pin "2") (pinfunction "2_2") (pintype "passive"))
      (node (ref "R21") (pin "1") (pinfunction "1_1") (pintype "passive"))
      (node (ref "U4") (pin "8") (pinfunction "VIN2-_8") (pintype "passive"))
    )
    (net (code "54") (name "/VIN3+") (class "Default")
      (node (ref "C14") (pin "2") (pinfunction "2_2") (pintype "passive"))
      (node (ref "R23") (pin "1") (pinfunction "1_1") (pintype "passive"))
      (node (ref "R26") (pin "2") (pinfunction "2_2") (pintype "passive"))
      (node (ref "U4") (pin "12") (pinfunction "VIN3+_12") (pintype "passive"))
    )
    (net (code "55") (name "/VIN3-") (class "Default")
      (node (ref "C28") (pin "2") (pinfunction "2_2") (pintype "passive"))
      (node (ref "R28") (pin "2") (pinfunction "2_2") (pintype "passive"))
      (node (ref "R29") (pin "1") (pinfunction "1_1") (pintype "passive"))
      (node (ref "U4") (pin "13") (pinfunction "VIN3-_13") (pintype "passive"))
    )
    (net (code "56") (name "/VIN4+") (class "Default")
      (node (ref "C29") (pin "2") (pinfunction "2_2") (pintype "passive"))
      (node (ref "R30") (pin "1") (pinfunction "1_1") (pintype "passive"))
      (node (ref "R32") (pin "2") (pinfunction "2_2") (pintype "passive"))
      (node (ref "U4") (pin "17") (pinfunction "VIN4+_17") (pintype "passive"))
    )
    (net (code "57") (name "/VIN4-") (class "Default")
      (node (ref "C31") (pin "2") (pinfunction "2_2") (pintype "passive"))
      (node (ref "R34") (pin "2") (pinfunction "2_2") (pintype "passive"))
      (node (ref "R36") (pin "1") (pinfunction "1_1") (pintype "passive"))
      (node (ref "U4") (pin "18") (pinfunction "VIN4-_18") (pintype "passive"))
    )
    (net (code "58") (name "/VOCM") (class "Default")
      (node (ref "C33") (pin "1") (pinfunction "1_1") (pintype "passive"))
      (node (ref "IC1") (pin "1") (pinfunction "OUT1_1") (pintype "passive"))
      (node (ref "IC1") (pin "2") (pinfunction "-_2") (pintype "passive"))
      (node (ref "U4") (pin "14") (pinfunction "VOCM3_14") (pintype "passive"))
      (node (ref "U4") (pin "19") (pinfunction "VOCM4_19") (pintype "passive"))
      (node (ref "U4") (pin "4") (pinfunction "VOCM1_4") (pintype "passive"))
      (node (ref "U4") (pin "9") (pinfunction "VOCM2_9") (pintype "passive"))
    )
    (net (code "59") (name "/VOUT1+") (class "Default")
      (node (ref "C3") (pin "1") (pinfunction "1_1") (pintype "passive"))
      (node (ref "R5") (pin "1") (pinfunction "1_1") (pintype "passive"))
      (node (ref "U4") (pin "36") (pinfunction "VOUT1+_36") (pintype "passive"))
    )
    (net (code "60") (name "/VOUT1-") (class "Default")
      (node (ref "C1") (pin "1") (pinfunction "1_1") (pintype "passive"))
      (node (ref "R2") (pin "1") (pinfunction "1_1") (pintype "passive"))
      (node (ref "U4") (pin "37") (pinfunction "VOUT1-_37") (pintype "passive"))
    )
    (net (code "61") (name "/VOUT2+") (class "Default")
      (node (ref "C13") (pin "1") (pinfunction "1_1") (pintype "passive"))
      (node (ref "R19") (pin "1") (pinfunction "1_1") (pintype "passive"))
      (node (ref "U4") (pin "31") (pinfunction "VOUT2+_31") (pintype "passive"))
    )
    (net (code "62") (name "/VOUT2-") (class "Default")
      (node (ref "C7") (pin "1") (pinfunction "1_1") (pintype "passive"))
      (node (ref "R15") (pin "1") (pinfunction "1_1") (pintype "passive"))
      (node (ref "U4") (pin "32") (pinfunction "VOUT2-_32") (pintype "passive"))
    )
    (net (code "63") (name "/VOUT3+") (class "Default")
      (node (ref "C28") (pin "1") (pinfunction "1_1") (pintype "passive"))
      (node (ref "R27") (pin "1") (pinfunction "1_1") (pintype "passive"))
      (node (ref "U4") (pin "26") (pinfunction "VOUT3+_26") (pintype "passive"))
    )
    (net (code "64") (name "/VOUT3-") (class "Default")
      (node (ref "C14") (pin "1") (pinfunction "1_1") (pintype "passive"))
      (node (ref "R25") (pin "1") (pinfunction "1_1") (pintype "passive"))
      (node (ref "U4") (pin "27") (pinfunction "VOUT3-_27") (pintype "passive"))
    )
    (net (code "65") (name "/VOUT4+") (class "Default")
      (node (ref "C31") (pin "1") (pinfunction "1_1") (pintype "passive"))
      (node (ref "R33") (pin "1") (pinfunction "1_1") (pintype "passive"))
      (node (ref "U4") (pin "21") (pinfunction "VOUT4+_21") (pintype "passive"))
    )
    (net (code "66") (name "/VOUT4-") (class "Default")
      (node (ref "C29") (pin "1") (pinfunction "1_1") (pintype "passive"))
      (node (ref "R31") (pin "1") (pinfunction "1_1") (pintype "passive"))
      (node (ref "U4") (pin "22") (pinfunction "VOUT4-_22") (pintype "passive"))
    )
    (net (code "67") (name "/WIFI_EN") (class "Default")
      (node (ref "JP6") (pin "3") (pinfunction "3_3") (pintype "passive"))
      (node (ref "U1") (pin "39") (pinfunction "PE8/FSMC_D5/T1CH1N_39") (pintype "passive"))
    )
    (net (code "68") (name "/WIFI_IO0") (class "Default")
      (node (ref "JP6") (pin "6") (pinfunction "6_6") (pintype "passive"))
      (node (ref "U1") (pin "41") (pinfunction "PE10/FSMC_D7/T1CH2N_41") (pintype "passive"))
    )
    (net (code "69") (name "/WIFI_IO2") (class "Default")
      (node (ref "JP6") (pin "4") (pinfunction "4_4") (pintype "passive"))
      (node (ref "U1") (pin "42") (pinfunction "PE11/FSMC_D8/T1C2_42") (pintype "passive"))
    )
    (net (code "70") (name "/WIFI_RST") (class "Default")
      (node (ref "JP6") (pin "5") (pinfunction "5_5") (pintype "passive"))
      (node (ref "U1") (pin "40") (pinfunction "PE9/FSMC_D6/T1C1_40") (pintype "passive"))
    )
    (net (code "71") (name "AGND") (class "Default")
      (node (ref "C35") (pin "1") (pinfunction "1_1") (pintype "passive"))
      (node (ref "E1") (pin "2") (pinfunction "K_2") (pintype "passive"))
      (node (ref "JP13") (pin "2") (pinfunction "2_2") (pintype "passive"))
      (node (ref "JP2") (pin "5") (pinfunction "5_5") (pintype "passive"))
      (node (ref "R20") (pin "1") (pinfunction "1_1") (pintype "passive"))
      (node (ref "R28") (pin "1") (pinfunction "1_1") (pintype "passive"))
      (node (ref "R34") (pin "1") (pinfunction "1_1") (pintype "passive"))
      (node (ref "R41") (pin "1") (pinfunction "1_1") (pintype "passive"))
      (node (ref "R7") (pin "1") (pinfunction "1_1") (pintype "passive"))
      (node (ref "U2") (pin "43") (pinfunction "AGND_43") (pintype "passive"))
      (node (ref "U2") (pin "54") (pinfunction "AGND_54") (pintype "passive"))
      (node (ref "U2") (pin "57") (pinfunction "VREFN_57") (pintype "passive"))
      (node (ref "U2") (pin "58") (pinfunction "AGND_58") (pintype "passive"))
      (node (ref "U2") (pin "59") (pinfunction "AGND_59") (pintype "passive"))
      (node (ref "U2") (pin "6") (pinfunction "AGND_6") (pintype "passive"))
      (node (ref "U3") (pin "25") (pinfunction "AGND_25") (pintype "power_in"))
      (node (ref "U6") (pin "2") (pinfunction "AGND_2") (pintype "passive"))
    )
    (net (code "72") (name "GND") (class "Default")
      (node (ref "C11") (pin "1") (pinfunction "1_1") (pintype "passive"))
      (node (ref "C12") (pin "2") (pinfunction "2_2") (pintype "passive"))
      (node (ref "C15") (pin "1") (pinfunction "1_1") (pintype "passive"))
      (node (ref "C16") (pin "1") (pinfunction "1_1") (pintype "passive"))
      (node (ref "C17") (pin "1") (pinfunction "1_1") (pintype "passive"))
      (node (ref "C18") (pin "1") (pinfunction "1_1") (pintype "passive"))
      (node (ref "C19") (pin "1") (pinfunction "1_1") (pintype "passive"))
      (node (ref "C20") (pin "1") (pinfunction "1_1") (pintype "passive"))
      (node (ref "C21") (pin "1") (pinfunction "1_1") (pintype "passive"))
      (node (ref "C22") (pin "1") (pinfunction "1_1") (pintype "passive"))
      (node (ref "C23") (pin "1") (pinfunction "1_1") (pintype "passive"))
      (node (ref "C24") (pin "1") (pinfunction "1_1") (pintype "passive"))
      (node (ref "C25") (pin "1") (pinfunction "1_1") (pintype "passive"))
      (node (ref "C26") (pin "1") (pinfunction "1_1") (pintype "passive"))
      (node (ref "C32") (pin "2") (pinfunction "2_2") (pintype "passive"))
      (node (ref "C33") (pin "2") (pinfunction "2_2") (pintype "passive"))
      (node (ref "C34") (pin "2") (pinfunction "2_2") (pintype "passive"))
      (node (ref "C36") (pin "1") (pinfunction "1_1") (pintype "passive"))
      (node (ref "C39") (pin "2") (pinfunction "2_2") (pintype "passive"))
      (node (ref "C4") (pin "1") (pinfunction "1_1") (pintype "passive"))
      (node (ref "C42") (pin "1") (pinfunction "1_1") (pintype "passive"))
      (node (ref "C43") (pin "1") (pinfunction "1_1") (pintype "passive"))
      (node (ref "C44") (pin "1") (pinfunction "1_1") (pintype "passive"))
      (node (ref "C45") (pin "1") (pinfunction "1_1") (pintype "passive"))
      (node (ref "C46") (pin "1") (pinfunction "1_1") (pintype "passive"))
      (node (ref "C47") (pin "1") (pinfunction "1_1") (pintype "passive"))
      (node (ref "C48") (pin "1") (pinfunction "1_1") (pintype "passive"))
      (node (ref "C49") (pin "1") (pinfunction "1_1") (pintype "passive"))
      (node (ref "C5") (pin "1") (pinfunction "1_1") (pintype "passive"))
      (node (ref "C50") (pin "1") (pinfunction "1_1") (pintype "passive"))
      (node (ref "C6") (pin "2") (pinfunction "2_2") (pintype "passive"))
      (node (ref "C8") (pin "2") (pinfunction "2_2") (pintype "passive"))
      (node (ref "C9") (pin "2") (pinfunction "2_2") (pintype "passive"))
      (node (ref "E2") (pin "2") (pinfunction "K_2") (pintype "passive"))
      (node (ref "E3") (pin "2") (pinfunction "K_2") (pintype "passive"))
      (node (ref "E4") (pin "2") (pinfunction "K_2") (pintype "passive"))
      (node (ref "E5") (pin "2") (pinfunction "K_2") (pintype "passive"))
      (node (ref "E6") (pin "2") (pinfunction "K_2") (pintype "passive"))
      (node (ref "JP1") (pin "10") (pinfunction "10_10") (pintype "passive"))
      (node (ref "JP1") (pin "12") (pinfunction "12_12") (pintype "passive"))
      (node (ref "JP1") (pin "14") (pinfunction "14_14") (pintype "passive"))
      (node (ref "JP1") (pin "16") (pinfunction "16_16") (pintype "passive"))
      (node (ref "JP1") (pin "18") (pinfunction "18_18") (pintype "passive"))
      (node (ref "JP1") (pin "20") (pinfunction "20_20") (pintype "passive"))
      (node (ref "JP1") (pin "4") (pinfunction "4_4") (pintype "passive"))
      (node (ref "JP1") (pin "6") (pinfunction "6_6") (pintype "passive"))
      (node (ref "JP1") (pin "8") (pinfunction "8_8") (pintype "passive"))
      (node (ref "JP4") (pin "2") (pinfunction "2_2") (pintype "passive"))
      (node (ref "JP5") (pin "2") (pinfunction "2_2") (pintype "passive"))
      (node (ref "JP6") (pin "2") (pinfunction "2_2") (pintype "passive"))
      (node (ref "OLED1") (pin "1") (pinfunction "GND_1") (pintype "passive"))
      (node (ref "Q2") (pin "3") (pinfunction "C_3") (pintype "passive"))
      (node (ref "R13") (pin "1") (pinfunction "1_1") (pintype "passive"))
      (node (ref "R37") (pin "1") (pinfunction "1_1") (pintype "passive"))
      (node (ref "R41") (pin "2") (pinfunction "2_2") (pintype "passive"))
      (node (ref "R42") (pin "2") (pinfunction "2_2") (pintype "passive"))
      (node (ref "R43") (pin "2") (pinfunction "2_2") (pintype "passive"))
      (node (ref "R9") (pin "1") (pinfunction "1_1") (pintype "passive"))
      (node (ref "SW1") (pin "2") (pinfunction "2_2") (pintype "passive"))
      (node (ref "U1") (pin "10") (pinfunction "VSS_5_10") (pintype "passive"))
      (node (ref "U1") (pin "20") (pinfunction "VSSA_20") (pintype "passive"))
      (node (ref "U1") (pin "27") (pinfunction "VSS_4_27") (pintype "passive"))
      (node (ref "U1") (pin "37") (pinfunction "PB2/BOOT1_37") (pintype "passive"))
      (node (ref "U1") (pin "74") (pinfunction "VSS_2_74") (pintype "passive"))
      (node (ref "U2") (pin "12") (pinfunction "DIN_12") (pintype "passive"))
      (node (ref "U2") (pin "21") (pinfunction "DGND_21") (pintype "passive"))
      (node (ref "U2") (pin "24") (pinfunction "DGND_24") (pintype "passive"))
      (node (ref "U2") (pin "25") (pinfunction "DGND_25") (pintype "passive"))
      (node (ref "U2") (pin "35") (pinfunction "~{PWDN8}_35") (pintype "passive"))
      (node (ref "U2") (pin "36") (pinfunction "~{PWDN7}_36") (pintype "passive"))
      (node (ref "U2") (pin "37") (pinfunction "~{PWDN6}_37") (pintype "passive"))
      (node (ref "U2") (pin "38") (pinfunction "~{PWDN5}_38") (pintype "passive"))
      (node (ref "U2") (pin "7") (pinfunction "DGND_7") (pintype "passive"))
      (node (ref "U2") (pin "8") (pinfunction "TEST0_8") (pintype "passive"))
      (node (ref "U2") (pin "9") (pinfunction "TEST1_9") (pintype "passive"))
      (node (ref "U3") (pin "18") (pinfunction "GND_18") (pintype "power_in"))
      (node (ref "U3") (pin "21") (pinfunction "GND_21") (pintype "power_in"))
      (node (ref "U3") (pin "26") (pinfunction "TEST_26") (pintype "input"))
      (node (ref "U3") (pin "7") (pinfunction "GND_7") (pintype "power_in"))
      (node (ref "U4") (pin "10") (pinfunction "VS-_10") (pintype "passive"))
      (node (ref "U4") (pin "15") (pinfunction "VS-_15") (pintype "passive"))
      (node (ref "U4") (pin "23") (pinfunction "VS-_23") (pintype "passive"))
      (node (ref "U4") (pin "24") (pinfunction "VS-_24") (pintype "passive"))
      (node (ref "U4") (pin "28") (pinfunction "VS-_28") (pintype "passive"))
      (node (ref "U4") (pin "29") (pinfunction "VS-_29") (pintype "passive"))
      (node (ref "U4") (pin "33") (pinfunction "VS-_33") (pintype "passive"))
      (node (ref "U4") (pin "34") (pinfunction "VS-_34") (pintype "passive"))
      (node (ref "U4") (pin "38") (pinfunction "VS-_38") (pintype "passive"))
      (node (ref "U4") (pin "5") (pinfunction "VS-_5") (pintype "passive"))
      (node (ref "U5") (pin "4") (pinfunction "GND_4") (pintype "passive"))
      (node (ref "U6") (pin "7") (pinfunction "DGND_7") (pintype "passive"))
      (node (ref "USB1") (pin "5") (pinfunction "GND_5") (pintype "passive"))
      (node (ref "V1") (pin "1") (pinfunction "GND_1") (pintype "passive"))
      (node (ref "V2") (pin "1") (pinfunction "GND_1") (pintype "passive"))
    )
    (net (code "73") (name "Net-(IC1A-+)") (class "Default")
      (node (ref "C34") (pin "1") (pinfunction "1_1") (pintype "passive"))
      (node (ref "IC1") (pin "3") (pinfunction "+_3") (pintype "passive"))
      (node (ref "U2") (pin "55") (pinfunction "VCOM_55") (pintype "passive"))
    )
    (net (code "74") (name "Net-(IC1B-+)") (class "Default")
      (node (ref "IC1") (pin "5") (pinfunction "+_5") (pintype "passive"))
      (node (ref "U6") (pin "1") (pinfunction "VOUT_1") (pintype "passive"))
    )
    (net (code "75") (name "Net-(LED+1-K)") (class "Default")
      (node (ref "LED+1") (pin "2") (pinfunction "K_2") (pintype "passive"))
      (node (ref "R43") (pin "1") (pinfunction "1_1") (pintype "passive"))
    )
    (net (code "76") (name "Net-(LED-1-A)") (class "Default")
      (node (ref "LED-1") (pin "1") (pinfunction "A_1") (pintype "passive"))
      (node (ref "R42") (pin "1") (pinfunction "1_1") (pintype "passive"))
    )
    (net (code "77") (name "Net-(LED1-K)") (class "Default")
      (node (ref "LED1") (pin "2") (pinfunction "K_2") (pintype "passive"))
      (node (ref "R22") (pin "1") (pinfunction "1_1") (pintype "passive"))
    )
    (net (code "78") (name "Net-(LED2-K)") (class "Default")
      (node (ref "LED2") (pin "2") (pinfunction "K_2") (pintype "passive"))
      (node (ref "R24") (pin "1") (pinfunction "1_1") (pintype "passive"))
    )
    (net (code "79") (name "Net-(LED_RX1-K)") (class "Default")
      (node (ref "LED_RX1") (pin "2") (pinfunction "K_2") (pintype "passive"))
      (node (ref "R39") (pin "1") (pinfunction "1_1") (pintype "passive"))
    )
    (net (code "80") (name "Net-(LED_TX1-K)") (class "Default")
      (node (ref "LED_TX1") (pin "2") (pinfunction "K_2") (pintype "passive"))
      (node (ref "R38") (pin "1") (pinfunction "1_1") (pintype "passive"))
    )
    (net (code "81") (name "Net-(Q1-B)") (class "Default")
      (node (ref "Q1") (pin "1") (pinfunction "B_1") (pintype "passive"))
      (node (ref "R35") (pin "2") (pinfunction "2_2") (pintype "passive"))
    )
    (net (code "82") (name "Net-(Q2-B)") (class "Default")
      (node (ref "C37") (pin "1") (pinfunction "1_1") (pintype "passive"))
      (node (ref "Q2") (pin "1") (pinfunction "B_1") (pintype "passive"))
      (node (ref "R40") (pin "1") (pinfunction "1_1") (pintype "passive"))
    )
    (net (code "83") (name "Net-(U1A-PE2{slash}TRACECK{slash}RSMC_A23)") (class "Default")
      (node (ref "R22") (pin "2") (pinfunction "2_2") (pintype "passive"))
      (node (ref "U1") (pin "1") (pinfunction "PE2/TRACECK/RSMC_A23_1") (pintype "passive"))
    )
    (net (code "84") (name "Net-(U1A-PE3{slash}TRACED0{slash}FSMC_A19)") (class "Default")
      (node (ref "R24") (pin "2") (pinfunction "2_2") (pintype "passive"))
      (node (ref "U1") (pin "2") (pinfunction "PE3/TRACED0/FSMC_A19_2") (pintype "passive"))
    )
    (net (code "85") (name "Net-(U1B-OSC_IN)") (class "Default")
      (node (ref "C11") (pin "2") (pinfunction "2_2") (pintype "passive"))
      (node (ref "R18") (pin "2") (pinfunction "2_2") (pintype "passive"))
      (node (ref "U1") (pin "12") (pinfunction "OSC_IN_12") (pintype "passive"))
      (node (ref "X1") (pin "2") (pinfunction "2_2") (pintype "passive"))
    )
    (net (code "86") (name "Net-(U1B-OSC_OUT)") (class "Default")
      (node (ref "C9") (pin "1") (pinfunction "1_1") (pintype "passive"))
      (node (ref "R18") (pin "1") (pinfunction "1_1") (pintype "passive"))
      (node (ref "U1") (pin "13") (pinfunction "OSC_OUT_13") (pintype "passive"))
      (node (ref "X1") (pin "1") (pinfunction "1_1") (pintype "passive"))
    )
    (net (code "87") (name "Net-(U1B-PDR_ON)") (class "Default")
      (node (ref "R12") (pin "2") (pinfunction "2_2") (pintype "passive"))
      (node (ref "R13") (pin "2") (pinfunction "2_2") (pintype "passive"))
      (node (ref "U1") (pin "99") (pinfunction "PDR_ON_99") (pintype "passive"))
    )
    (net (code "88") (name "Net-(U1B-VCAP1)") (class "Default")
      (node (ref "C6") (pin "1") (pinfunction "1_1") (pintype "passive"))
      (node (ref "U1") (pin "49") (pinfunction "VCAP1_49") (pintype "passive"))
    )
    (net (code "89") (name "Net-(U1B-VCAP2)") (class "Default")
      (node (ref "C8") (pin "1") (pinfunction "1_1") (pintype "passive"))
      (node (ref "U1") (pin "73") (pinfunction "VCAP2_73") (pintype "passive"))
    )
    (net (code "90") (name "Net-(U3-3V3OUT)") (class "Default")
      (node (ref "C32") (pin "1") (pinfunction "1_1") (pintype "passive"))
      (node (ref "U3") (pin "17") (pinfunction "3V3OUT_17") (pintype "power_in"))
    )
    (net (code "91") (name "Net-(U3-RXLED#)") (class "Default")
      (node (ref "R39") (pin "2") (pinfunction "2_2") (pintype "passive"))
      (node (ref "U3") (pin "22") (pinfunction "RXLED#_22") (pintype "open_collector"))
    )
    (net (code "92") (name "Net-(U3-TXLED#)") (class "Default")
      (node (ref "R38") (pin "2") (pinfunction "2_2") (pintype "passive"))
      (node (ref "U3") (pin "23") (pinfunction "TXLED#_23") (pintype "output"))
    )
    (net (code "93") (name "Net-(U5-TRIM)") (class "Default")
      (node (ref "C44") (pin "2") (pinfunction "2_2") (pintype "passive"))
      (node (ref "U5") (pin "5") (pinfunction "TRIM_5") (pintype "passive"))
    )
    (net (code "94") (name "REF2.5V") (class "Default")
      (node (ref "C35") (pin "2") (pinfunction "2_2") (pintype "passive"))
      (node (ref "E1") (pin "1") (pinfunction "A_1") (pintype "passive"))
      (node (ref "U2") (pin "56") (pinfunction "VREFP_56") (pintype "passive"))
      (node (ref "U5") (pin "6") (pinfunction "VOUT_6") (pintype "passive"))
      (node (ref "U6") (pin "3") (pinfunction "VREF_3") (pintype "passive"))
    )
    (net (code "95") (name "VCC+5") (class "Default")
      (node (ref "C36") (pin "2") (pinfunction "2_2") (pintype "passive"))
      (node (ref "C39") (pin "1") (pinfunction "1_1") (pintype "passive"))
      (node (ref "C42") (pin "2") (pinfunction "2_2") (pintype "passive"))
      (node (ref "C45") (pin "2") (pinfunction "2_2") (pintype "passive"))
      (node (ref "C47") (pin "2") (pinfunction "2_2") (pintype "passive"))
      (node (ref "C48") (pin "2") (pinfunction "2_2") (pintype "passive"))
      (node (ref "E2") (pin "1") (pinfunction "A_1") (pintype "passive"))
      (node (ref "E3") (pin "1") (pinfunction "A_1") (pintype "passive"))
      (node (ref "E5") (pin "1") (pinfunction "A_1") (pintype "passive"))
      (node (ref "IC1") (pin "8") (pinfunction "V+_8") (pintype "power_in"))
      (node (ref "JP4") (pin "1") (pinfunction "1_1") (pintype "passive"))
      (node (ref "JP5") (pin "1") (pinfunction "1_1") (pintype "passive"))
      (node (ref "LED+1") (pin "1") (pinfunction "A_1") (pintype "passive"))
      (node (ref "LED_RX1") (pin "1") (pinfunction "A_1") (pintype "passive"))
      (node (ref "LED_TX1") (pin "1") (pinfunction "A_1") (pintype "passive"))
      (node (ref "U2") (pin "44") (pinfunction "AVDD_44") (pintype "passive"))
      (node (ref "U2") (pin "5") (pinfunction "AVDD_5") (pintype "passive"))
      (node (ref "U2") (pin "53") (pinfunction "AVDD_53") (pintype "passive"))
      (node (ref "U2") (pin "60") (pinfunction "AVDD_60") (pintype "passive"))
      (node (ref "U3") (pin "20") (pinfunction "VCC_20") (pintype "power_in"))
      (node (ref "U3") (pin "4") (pinfunction "VCCIO_4") (pintype "power_in"))
      (node (ref "U4") (pin "1") (pinfunction "~{PD}1_1") (pintype "passive"))
      (node (ref "U4") (pin "11") (pinfunction "~{PD}3_11") (pintype "passive"))
      (node (ref "U4") (pin "16") (pinfunction "~{PD}4_16") (pintype "passive"))
      (node (ref "U4") (pin "20") (pinfunction "VS4+_20") (pintype "passive"))
      (node (ref "U4") (pin "25") (pinfunction "VS3+_25") (pintype "passive"))
      (node (ref "U4") (pin "30") (pinfunction "VS2+_30") (pintype "passive"))
      (node (ref "U4") (pin "35") (pinfunction "VS1+_35") (pintype "passive"))
      (node (ref "U4") (pin "6") (pinfunction "~{PD}2_6") (pintype "passive"))
      (node (ref "U5") (pin "2") (pinfunction "IN_2") (pintype "passive"))
      (node (ref "U6") (pin "8") (pinfunction "VDD_8") (pintype "passive"))
      (node (ref "USB1") (pin "1") (pinfunction "+5V_1") (pintype "passive"))
      (node (ref "V1") (pin "3") (pinfunction "Vin_3") (pintype "passive"))
      (node (ref "V2") (pin "3") (pinfunction "Vin_3") (pintype "passive"))
    )
    (net (code "96") (name "VCC-5") (class "Default")
      (node (ref "C49") (pin "2") (pinfunction "2_2") (pintype "passive"))
      (node (ref "C50") (pin "2") (pinfunction "2_2") (pintype "passive"))
      (node (ref "IC1") (pin "4") (pinfunction "V-_4") (pintype "power_in"))
      (node (ref "JP4") (pin "3") (pinfunction "3_3") (pintype "passive"))
      (node (ref "JP5") (pin "3") (pinfunction "3_3") (pintype "passive"))
      (node (ref "LED-1") (pin "2") (pinfunction "K_2") (pintype "passive"))
    )
    (net (code "97") (name "VCC1.8") (class "Default")
      (node (ref "C43") (pin "2") (pinfunction "2_2") (pintype "passive"))
      (node (ref "E4") (pin "1") (pinfunction "A_1") (pintype "passive"))
      (node (ref "U2") (pin "26") (pinfunction "DVDD_26") (pintype "passive"))
      (node (ref "V1") (pin "2") (pinfunction "Vout_2") (pintype "passive"))
    )
    (net (code "98") (name "VCC3.3") (class "Default")
      (node (ref "C15") (pin "2") (pinfunction "2_2") (pintype "passive"))
      (node (ref "C16") (pin "2") (pinfunction "2_2") (pintype "passive"))
      (node (ref "C17") (pin "2") (pinfunction "2_2") (pintype "passive"))
      (node (ref "C18") (pin "2") (pinfunction "2_2") (pintype "passive"))
      (node (ref "C19") (pin "2") (pinfunction "2_2") (pintype "passive"))
      (node (ref "C20") (pin "2") (pinfunction "2_2") (pintype "passive"))
      (node (ref "C21") (pin "2") (pinfunction "2_2") (pintype "passive"))
      (node (ref "C22") (pin "2") (pinfunction "2_2") (pintype "passive"))
      (node (ref "C23") (pin "2") (pinfunction "2_2") (pintype "passive"))
      (node (ref "C24") (pin "2") (pinfunction "2_2") (pintype "passive"))
      (node (ref "C25") (pin "2") (pinfunction "2_2") (pintype "passive"))
      (node (ref "C26") (pin "2") (pinfunction "2_2") (pintype "passive"))
      (node (ref "C37") (pin "2") (pinfunction "2_2") (pintype "passive"))
      (node (ref "C4") (pin "2") (pinfunction "2_2") (pintype "passive"))
      (node (ref "C46") (pin "2") (pinfunction "2_2") (pintype "passive"))
      (node (ref "C5") (pin "2") (pinfunction "2_2") (pintype "passive"))
      (node (ref "E6") (pin "1") (pinfunction "A_1") (pintype "passive"))
      (node (ref "JP1") (pin "1") (pinfunction "1_1") (pintype "passive"))
      (node (ref "JP1") (pin "2") (pinfunction "2_2") (pintype "passive"))
      (node (ref "JP6") (pin "7") (pinfunction "7_7") (pintype "passive"))
      (node (ref "LED1") (pin "1") (pinfunction "A_1") (pintype "passive"))
      (node (ref "LED2") (pin "1") (pinfunction "A_1") (pintype "passive"))
      (node (ref "OLED1") (pin "2") (pinfunction "VCC_2") (pintype "passive"))
      (node (ref "Q1") (pin "2") (pinfunction "E_2") (pintype "passive"))
      (node (ref "R10") (pin "1") (pinfunction "1_1") (pintype "passive"))
      (node (ref "R12") (pin "1") (pinfunction "1_1") (pintype "passive"))
      (node (ref "R16") (pin "2") (pinfunction "2_2") (pintype "passive"))
      (node (ref "R4") (pin "1") (pinfunction "1_1") (pintype "passive"))
      (node (ref "R6") (pin "1") (pinfunction "1_1") (pintype "passive"))
      (node (ref "R8") (pin "1") (pinfunction "1_1") (pintype "passive"))
      (node (ref "U1") (pin "100") (pinfunction "VDD_3_100") (pintype "passive"))
      (node (ref "U1") (pin "11") (pinfunction "VDD_5_11") (pintype "passive"))
      (node (ref "U1") (pin "19") (pinfunction "VDD12_19") (pintype "passive"))
      (node (ref "U1") (pin "21") (pinfunction "VREF+_21") (pintype "passive"))
      (node (ref "U1") (pin "22") (pinfunction "VDDA_22") (pintype "passive"))
      (node (ref "U1") (pin "28") (pinfunction "VDD_4_28") (pintype "passive"))
      (node (ref "U1") (pin "50") (pinfunction "VDD_1_50") (pintype "passive"))
      (node (ref "U1") (pin "6") (pinfunction "VBAT_6") (pintype "passive"))
      (node (ref "U1") (pin "75") (pinfunction "VDD_2_75") (pintype "passive"))
      (node (ref "U2") (pin "22") (pinfunction "IOVDD_22") (pintype "passive"))
      (node (ref "U2") (pin "23") (pinfunction "IOVDD_23") (pintype "passive"))
      (node (ref "U2") (pin "39") (pinfunction "~{PWDN4}_39") (pintype "passive"))
      (node (ref "U2") (pin "40") (pinfunction "~{PWDN3}_40") (pintype "passive"))
      (node (ref "U2") (pin "41") (pinfunction "~{PWDN2}_41") (pintype "passive"))
      (node (ref "U2") (pin "42") (pinfunction "~{PWDN1}_42") (pintype "passive"))
      (node (ref "V2") (pin "2") (pinfunction "Vout_2") (pintype "passive"))
    )
    (net (code "99") (name "unconnected-(JP1-Pad11)") (class "Default")
      (node (ref "JP1") (pin "11") (pinfunction "11_11") (pintype "passive"))
    )
    (net (code "100") (name "unconnected-(JP1-Pad17)") (class "Default")
      (node (ref "JP1") (pin "17") (pinfunction "17_17") (pintype "passive"))
    )
    (net (code "101") (name "unconnected-(JP1-Pad19)") (class "Default")
      (node (ref "JP1") (pin "19") (pinfunction "19_19") (pintype "passive"))
    )
    (net (code "102") (name "unconnected-(U1A-PA0{slash}WKUP{slash}ADC123_IN0{slash}T2C1ETR{slash}T5C1{slash}T8ETR-Pad23)") (class "Default")
      (node (ref "U1") (pin "23") (pinfunction "PA0/WKUP/ADC123_IN0/T2C1ETR/T5C1/T8ETR_23") (pintype "passive"))
    )
    (net (code "103") (name "unconnected-(U1A-PA1{slash}ADC123_IN1{slash}T5C2{slash}T2C2-Pad24)") (class "Default")
      (node (ref "U1") (pin "24") (pinfunction "PA1/ADC123_IN1/T5C2/T2C2_24") (pintype "passive"))
    )
    (net (code "104") (name "unconnected-(U1A-PA11{slash}CAN_Rx{slash}T1C4{slash}USBDM-Pad70)") (class "Default")
      (node (ref "U1") (pin "70") (pinfunction "PA11/CAN_Rx/T1C4/USBDM_70") (pintype "passive"))
    )
    (net (code "105") (name "unconnected-(U1A-PA12{slash}CAN_Tx{slash}T1ETR{slash}USBDP-Pad71)") (class "Default")
      (node (ref "U1") (pin "71") (pinfunction "PA12/CAN_Tx/T1ETR/USBDP_71") (pintype "passive"))
    )
    (net (code "106") (name "unconnected-(U1A-PB0{slash}ADC123_IN8{slash}T3C3{slash}T8C2N{slash}T1C2N-Pad35)") (class "Default")
      (node (ref "U1") (pin "35") (pinfunction "PB0/ADC123_IN8/T3C3/T8C2N/T1C2N_35") (pintype "passive"))
    )
    (net (code "107") (name "unconnected-(U1A-PB1{slash}ADC123_IN9{slash}T3C4{slash}T8C3N{slash}T1C3N-Pad36)") (class "Default")
      (node (ref "U1") (pin "36") (pinfunction "PB1/ADC123_IN9/T3C4/T8C3N/T1C3N_36") (pintype "passive"))
    )
    (net (code "108") (name "unconnected-(U1A-PB5{slash}I2C1_SMBA{slash}I2S3_SD{slash}SPI3_MOSI{slash}T3C2{slash}SPI1_MOSI-Pad91)") (class "Default")
      (node (ref "U1") (pin "91") (pinfunction "PB5/I2C1_SMBA/I2S3_SD/SPI3_MOSI/T3C2/SPI1_MOSI_91") (pintype "passive"))
    )
    (net (code "109") (name "unconnected-(U1A-PB6{slash}I2C1_SCL{slash}T4C1{slash}USART1_Tx-Pad92)") (class "Default")
      (node (ref "U1") (pin "92") (pinfunction "PB6/I2C1_SCL/T4C1/USART1_Tx_92") (pintype "passive"))
    )
    (net (code "110") (name "unconnected-(U1A-PB7{slash}I2C1_SDA{slash}FSMC_NADV{slash}USART1_Rx-Pad93)") (class "Default")
      (node (ref "U1") (pin "93") (pinfunction "PB7/I2C1_SDA/FSMC_NADV/USART1_Rx_93") (pintype "passive"))
    )
    (net (code "111") (name "unconnected-(U1A-PB8{slash}SDIO_D4{slash}I2C1_SCL{slash}T4C3(7){slash}CAN_Rx-Pad95)") (class "Default")
      (node (ref "U1") (pin "95") (pinfunction "PB8/SDIO_D4/I2C1_SCL/T4C3(7)/CAN_Rx_95") (pintype "passive"))
    )
    (net (code "112") (name "unconnected-(U1A-PB9{slash}SDIO_D5{slash}I2C1_SDA{slash}T4C4{slash}CAN_Tx-Pad96)") (class "Default")
      (node (ref "U1") (pin "96") (pinfunction "PB9/SDIO_D5/I2C1_SDA/T4C4/CAN_Tx_96") (pintype "passive"))
    )
    (net (code "113") (name "unconnected-(U1A-PB10{slash}USART3_Tx{slash}I2C2_SCL{slash}T2C3-Pad47)") (class "Default")
      (node (ref "U1") (pin "47") (pinfunction "PB10/USART3_Tx/I2C2_SCL/T2C3_47") (pintype "passive"))
    )
    (net (code "114") (name "unconnected-(U1A-PB11{slash}USART3_Rx{slash}I2C2_SDA{slash}T2C4-Pad48)") (class "Default")
      (node (ref "U1") (pin "48") (pinfunction "PB11/USART3_Rx/I2C2_SDA/T2C4_48") (pintype "passive"))
    )
    (net (code "115") (name "unconnected-(U1A-PB12{slash}I2S2_WS{slash}T1BKIN{slash}SPI2_NSS{slash}I2C2_SMBA-Pad51)") (class "Default")
      (node (ref "U1") (pin "51") (pinfunction "PB12/I2S2_WS/T1BKIN/SPI2_NSS/I2C2_SMBA_51") (pintype "passive"))
    )
    (net (code "116") (name "unconnected-(U1A-PC0{slash}ADC123_IN10-Pad15)") (class "Default")
      (node (ref "U1") (pin "15") (pinfunction "PC0/ADC123_IN10_15") (pintype "passive"))
    )
    (net (code "117") (name "unconnected-(U1A-PC1{slash}ADC123_IN11-Pad16)") (class "Default")
      (node (ref "U1") (pin "16") (pinfunction "PC1/ADC123_IN11_16") (pintype "passive"))
    )
    (net (code "118") (name "unconnected-(U1A-PC2{slash}ADC123_IN12-Pad17)") (class "Default")
      (node (ref "U1") (pin "17") (pinfunction "PC2/ADC123_IN12_17") (pintype "passive"))
    )
    (net (code "119") (name "unconnected-(U1A-PC3{slash}ADC123_IN13-Pad18)") (class "Default")
      (node (ref "U1") (pin "18") (pinfunction "PC3/ADC123_IN13_18") (pintype "passive"))
    )
    (net (code "120") (name "unconnected-(U1A-PC4{slash}ADC123_IN14-Pad33)") (class "Default")
      (node (ref "U1") (pin "33") (pinfunction "PC4/ADC123_IN14_33") (pintype "passive"))
    )
    (net (code "121") (name "unconnected-(U1A-PC5{slash}ADC123_IN15-Pad34)") (class "Default")
      (node (ref "U1") (pin "34") (pinfunction "PC5/ADC123_IN15_34") (pintype "passive"))
    )
    (net (code "122") (name "unconnected-(U1A-PC6{slash}I2S2_MCK{slash}T8C1{slash}T3C1{slash}SDIO_D6-Pad63)") (class "Default")
      (node (ref "U1") (pin "63") (pinfunction "PC6/I2S2_MCK/T8C1/T3C1/SDIO_D6_63") (pintype "passive"))
    )
    (net (code "123") (name "unconnected-(U1A-PC7{slash}I2S3_MCK{slash}T8C2{slash}T3C2{slash}SDIO_D7-Pad64)") (class "Default")
      (node (ref "U1") (pin "64") (pinfunction "PC7/I2S3_MCK/T8C2/T3C2/SDIO_D7_64") (pintype "passive"))
    )
    (net (code "124") (name "unconnected-(U1A-PC8{slash}T8C3{slash}T3C3{slash}SDIO_D0-Pad65)") (class "Default")
      (node (ref "U1") (pin "65") (pinfunction "PC8/T8C3/T3C3/SDIO_D0_65") (pintype "passive"))
    )
    (net (code "125") (name "unconnected-(U1A-PC9{slash}T8C4{slash}T3C4{slash}SDIO_D1-Pad66)") (class "Default")
      (node (ref "U1") (pin "66") (pinfunction "PC9/T8C4/T3C4/SDIO_D1_66") (pintype "passive"))
    )
    (net (code "126") (name "unconnected-(U1A-PC13-TAMPER-RTC-Pad7)") (class "Default")
      (node (ref "U1") (pin "7") (pinfunction "PC13-TAMPER-RTC_7") (pintype "passive"))
    )
    (net (code "127") (name "unconnected-(U1A-PD2{slash}UART5_Rx{slash}T3ETR{slash}SDIO_CMD-Pad83)") (class "Default")
      (node (ref "U1") (pin "83") (pinfunction "PD2/UART5_Rx/T3ETR/SDIO_CMD_83") (pintype "passive"))
    )
    (net (code "128") (name "unconnected-(U1A-PD3{slash}FSMC_CLK-Pad84)") (class "Default")
      (node (ref "U1") (pin "84") (pinfunction "PD3/FSMC_CLK_84") (pintype "passive"))
    )
    (net (code "129") (name "unconnected-(U1A-PD4{slash}FSMC_NOE-Pad85)") (class "Default")
      (node (ref "U1") (pin "85") (pinfunction "PD4/FSMC_NOE_85") (pintype "passive"))
    )
    (net (code "130") (name "unconnected-(U1A-PD5{slash}USART2_Tx{slash}FSMC_NWE-Pad86)") (class "Default")
      (node (ref "U1") (pin "86") (pinfunction "PD5/USART2_Tx/FSMC_NWE_86") (pintype "passive"))
    )
    (net (code "131") (name "unconnected-(U1A-PD6{slash}USART2_Rx{slash}FSMC_NWAIT-Pad87)") (class "Default")
      (node (ref "U1") (pin "87") (pinfunction "PD6/USART2_Rx/FSMC_NWAIT_87") (pintype "passive"))
    )
    (net (code "132") (name "unconnected-(U1A-PD7{slash}FSMC_NE1{slash}FSMC_NCE2-Pad88)") (class "Default")
      (node (ref "U1") (pin "88") (pinfunction "PD7/FSMC_NE1/FSMC_NCE2_88") (pintype "passive"))
    )
    (net (code "133") (name "unconnected-(U1A-PE0{slash}T4_ETR{slash}FSMC_NBL0-Pad97)") (class "Default")
      (node (ref "U1") (pin "97") (pinfunction "PE0/T4_ETR/FSMC_NBL0_97") (pintype "passive"))
    )
    (net (code "134") (name "unconnected-(U1A-PE1{slash}FSMC_NBL1-Pad98)") (class "Default")
      (node (ref "U1") (pin "98") (pinfunction "PE1/FSMC_NBL1_98") (pintype "passive"))
    )
    (net (code "135") (name "unconnected-(U1A-PE4{slash}TRACED1{slash}FSMC_A20-Pad3)") (class "Default")
      (node (ref "U1") (pin "3") (pinfunction "PE4/TRACED1/FSMC_A20_3") (pintype "passive"))
    )
    (net (code "136") (name "unconnected-(U1A-PE5{slash}TRACED2{slash}FSMC_A21-Pad4)") (class "Default")
      (node (ref "U1") (pin "4") (pinfunction "PE5/TRACED2/FSMC_A21_4") (pintype "passive"))
    )
    (net (code "137") (name "unconnected-(U1A-PE6{slash}TRACED3{slash}FSMC_A22-Pad5)") (class "Default")
      (node (ref "U1") (pin "5") (pinfunction "PE6/TRACED3/FSMC_A22_5") (pintype "passive"))
    )
    (net (code "138") (name "unconnected-(U1A-PE7{slash}FSMC_D4{slash}T1ETR-Pad38)") (class "Default")
      (node (ref "U1") (pin "38") (pinfunction "PE7/FSMC_D4/T1ETR_38") (pintype "passive"))
    )
    (net (code "139") (name "unconnected-(U1A-PE12{slash}FSMC_D9{slash}T1CH3N-Pad43)") (class "Default")
      (node (ref "U1") (pin "43") (pinfunction "PE12/FSMC_D9/T1CH3N_43") (pintype "passive"))
    )
    (net (code "140") (name "unconnected-(U1A-PE13{slash}FSMC_D10{slash}T1C3-Pad44)") (class "Default")
      (node (ref "U1") (pin "44") (pinfunction "PE13/FSMC_D10/T1C3_44") (pintype "passive"))
    )
    (net (code "141") (name "unconnected-(U1A-PE14{slash}FSMC_D11{slash}T1C4-Pad45)") (class "Default")
      (node (ref "U1") (pin "45") (pinfunction "PE14/FSMC_D11/T1C4_45") (pintype "passive"))
    )
    (net (code "142") (name "unconnected-(U1A-PE15{slash}FSMC_D12{slash}T1BKIN-Pad46)") (class "Default")
      (node (ref "U1") (pin "46") (pinfunction "PE15/FSMC_D12/T1BKIN_46") (pintype "passive"))
    )
    (net (code "143") (name "unconnected-(U1B-PC14-OSC32_IN-Pad8)") (class "Default")
      (node (ref "U1") (pin "8") (pinfunction "PC14-OSC32_IN_8") (pintype "passive"))
    )
    (net (code "144") (name "unconnected-(U1B-PC15-OSC32_OUT-Pad9)") (class "Default")
      (node (ref "U1") (pin "9") (pinfunction "PC15-OSC32_OUT_9") (pintype "passive"))
    )
    (net (code "145") (name "unconnected-(U2-AINN5-Pad52)") (class "Default")
      (node (ref "U2") (pin "52") (pinfunction "AINN5_52") (pintype "passive"))
    )
    (net (code "146") (name "unconnected-(U2-AINN6-Pad50)") (class "Default")
      (node (ref "U2") (pin "50") (pinfunction "AINN6_50") (pintype "passive"))
    )
    (net (code "147") (name "unconnected-(U2-AINN7-Pad48)") (class "Default")
      (node (ref "U2") (pin "48") (pinfunction "AINN7_48") (pintype "passive"))
    )
    (net (code "148") (name "unconnected-(U2-AINN8-Pad46)") (class "Default")
      (node (ref "U2") (pin "46") (pinfunction "AINN8_46") (pintype "passive"))
    )
    (net (code "149") (name "unconnected-(U2-AINP5-Pad51)") (class "Default")
      (node (ref "U2") (pin "51") (pinfunction "AINP5_51") (pintype "passive"))
    )
    (net (code "150") (name "unconnected-(U2-AINP6-Pad49)") (class "Default")
      (node (ref "U2") (pin "49") (pinfunction "AINP6_49") (pintype "passive"))
    )
    (net (code "151") (name "unconnected-(U2-AINP7-Pad47)") (class "Default")
      (node (ref "U2") (pin "47") (pinfunction "AINP7_47") (pintype "passive"))
    )
    (net (code "152") (name "unconnected-(U2-AINP8-Pad45)") (class "Default")
      (node (ref "U2") (pin "45") (pinfunction "AINP8_45") (pintype "passive"))
    )
    (net (code "153") (name "unconnected-(U2-DOUT2-Pad19)") (class "Default")
      (node (ref "U2") (pin "19") (pinfunction "DOUT2_19") (pintype "passive"))
    )
    (net (code "154") (name "unconnected-(U2-DOUT3-Pad18)") (class "Default")
      (node (ref "U2") (pin "18") (pinfunction "DOUT3_18") (pintype "passive"))
    )
    (net (code "155") (name "unconnected-(U2-DOUT4-Pad17)") (class "Default")
      (node (ref "U2") (pin "17") (pinfunction "DOUT4_17") (pintype "passive"))
    )
    (net (code "156") (name "unconnected-(U2-DOUT5-Pad16)") (class "Default")
      (node (ref "U2") (pin "16") (pinfunction "DOUT5_16") (pintype "passive"))
    )
    (net (code "157") (name "unconnected-(U2-DOUT6-Pad15)") (class "Default")
      (node (ref "U2") (pin "15") (pinfunction "DOUT6_15") (pintype "passive"))
    )
    (net (code "158") (name "unconnected-(U2-DOUT7-Pad14)") (class "Default")
      (node (ref "U2") (pin "14") (pinfunction "DOUT7_14") (pintype "passive"))
    )
    (net (code "159") (name "unconnected-(U2-DOUT8-Pad13)") (class "Default")
      (node (ref "U2") (pin "13") (pinfunction "DOUT8_13") (pintype "passive"))
    )
    (net (code "160") (name "unconnected-(U3-CTS#-Pad11)") (class "Default")
      (node (ref "U3") (pin "11") (pinfunction "CTS#_11") (pintype "input+no_connect"))
    )
    (net (code "161") (name "unconnected-(U3-DCD#-Pad10)") (class "Default")
      (node (ref "U3") (pin "10") (pinfunction "DCD#_10") (pintype "input+no_connect"))
    )
    (net (code "162") (name "unconnected-(U3-DSR#-Pad9)") (class "Default")
      (node (ref "U3") (pin "9") (pinfunction "DSR#_9") (pintype "input+no_connect"))
    )
    (net (code "163") (name "unconnected-(U3-NC-Pad8)") (class "Default")
      (node (ref "U3") (pin "8") (pinfunction "NC_8") (pintype "passive"))
    )
    (net (code "164") (name "unconnected-(U3-NC-Pad24)") (class "Default")
      (node (ref "U3") (pin "24") (pinfunction "NC_24") (pintype "passive"))
    )
    (net (code "165") (name "unconnected-(U3-OSCI-Pad27)") (class "Default")
      (node (ref "U3") (pin "27") (pinfunction "OSCI_27") (pintype "input+no_connect"))
    )
    (net (code "166") (name "unconnected-(U3-OXCO-Pad28)") (class "Default")
      (node (ref "U3") (pin "28") (pinfunction "OXCO_28") (pintype "output"))
    )
    (net (code "167") (name "unconnected-(U3-PWREN#-Pad14)") (class "Default")
      (node (ref "U3") (pin "14") (pinfunction "PWREN#_14") (pintype "output"))
    )
    (net (code "168") (name "unconnected-(U3-RESET#-Pad19)") (class "Default")
      (node (ref "U3") (pin "19") (pinfunction "RESET#_19") (pintype "input+no_connect"))
    )
    (net (code "169") (name "unconnected-(U3-RI#-Pad6)") (class "Default")
      (node (ref "U3") (pin "6") (pinfunction "RI#_6") (pintype "input+no_connect"))
    )
    (net (code "170") (name "unconnected-(U3-SLEEP#-Pad12)") (class "Default")
      (node (ref "U3") (pin "12") (pinfunction "SLEEP#_12") (pintype "output"))
    )
    (net (code "171") (name "unconnected-(U3-TXDEN#-Pad13)") (class "Default")
      (node (ref "U3") (pin "13") (pinfunction "TXDEN#_13") (pintype "open_collector"))
    )
    (net (code "172") (name "unconnected-(U5-NC-Pad1)") (class "Default")
      (node (ref "U5") (pin "1") (pinfunction "NC_1") (pintype "passive"))
    )
    (net (code "173") (name "unconnected-(U5-NC-Pad7)") (class "Default")
      (node (ref "U5") (pin "7") (pinfunction "NC_7") (pintype "passive"))
    )
    (net (code "174") (name "unconnected-(U5-NC-Pad8)") (class "Default")
      (node (ref "U5") (pin "8") (pinfunction "NC_8") (pintype "passive"))
    )
    (net (code "175") (name "unconnected-(U5-TEMP-Pad3)") (class "Default")
      (node (ref "U5") (pin "3") (pinfunction "TEMP_3") (pintype "passive"))
    )
    (net (code "176") (name "unconnected-(USB1-ID-Pad4)") (class "Default")
      (node (ref "USB1") (pin "4") (pinfunction "ID_4") (pintype "passive"))
    )
  )
)
